# MonthCalendar_Controller_v0_9.net
KiCad netlist of a schematic drawn in EAGLE
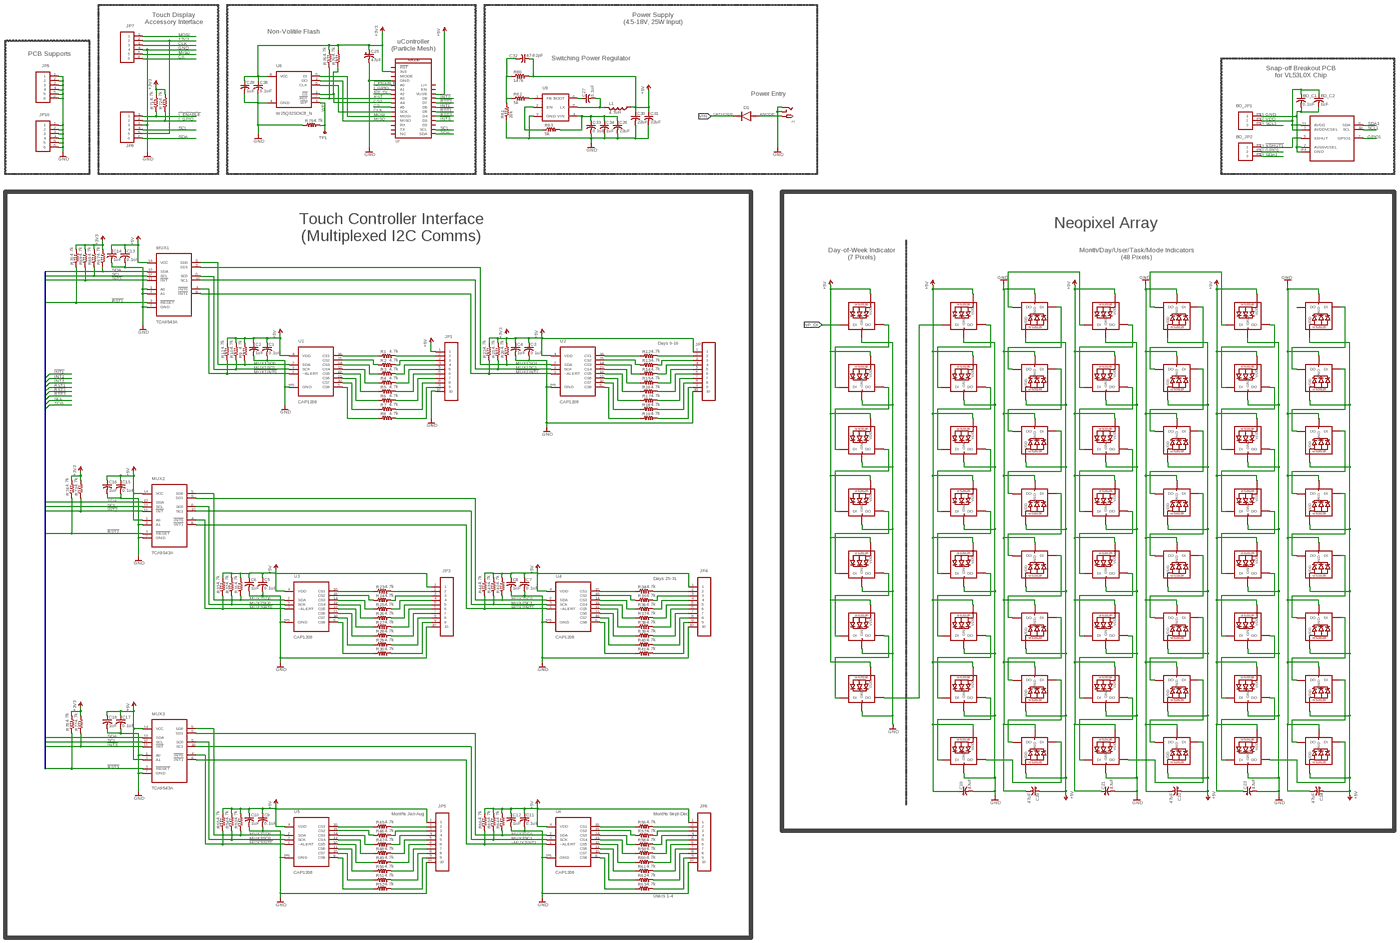
[diagram p0: schematic, sheet 1, overview]
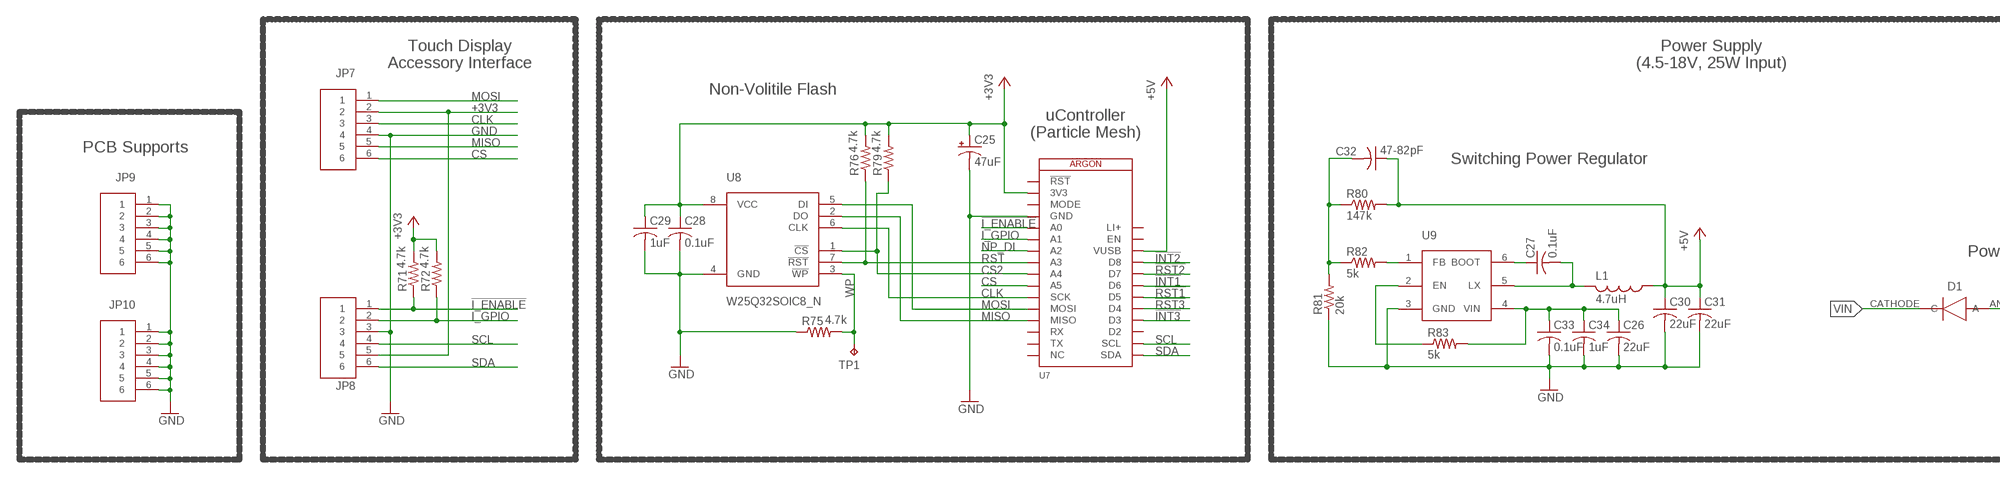
[diagram p1: schematic, sheet 1, part 1 of 4]
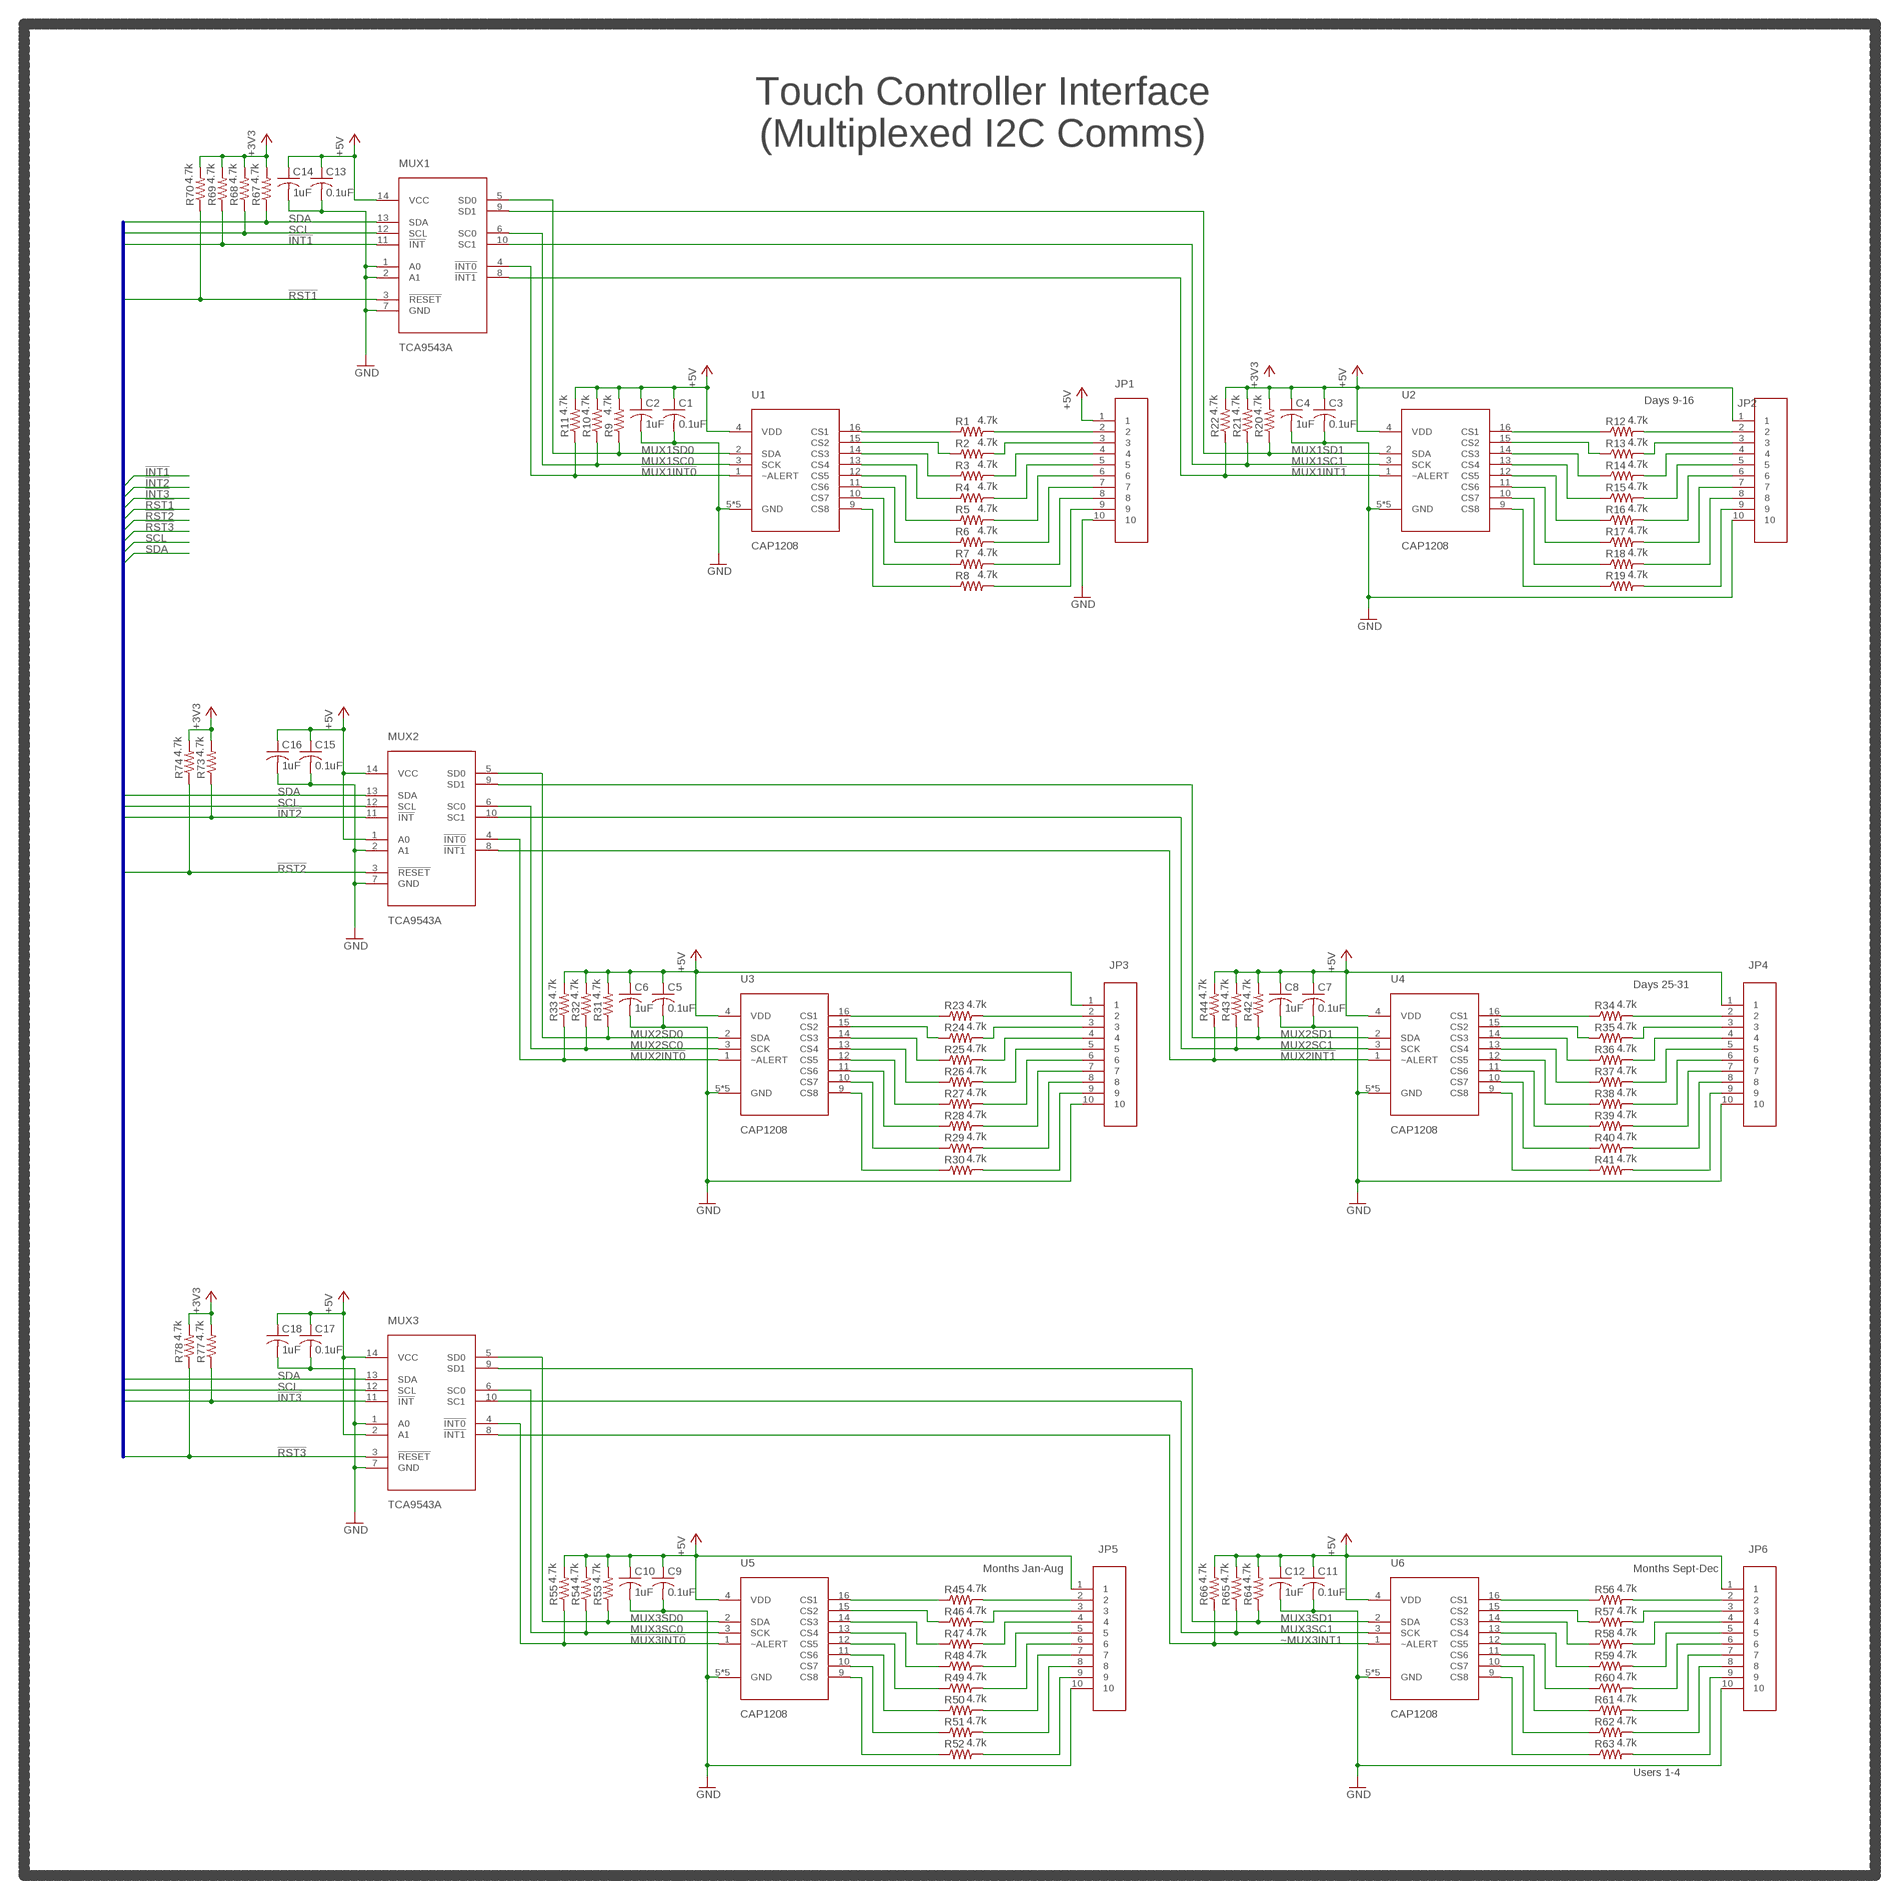
[diagram p2: schematic, sheet 1, part 2 of 4]
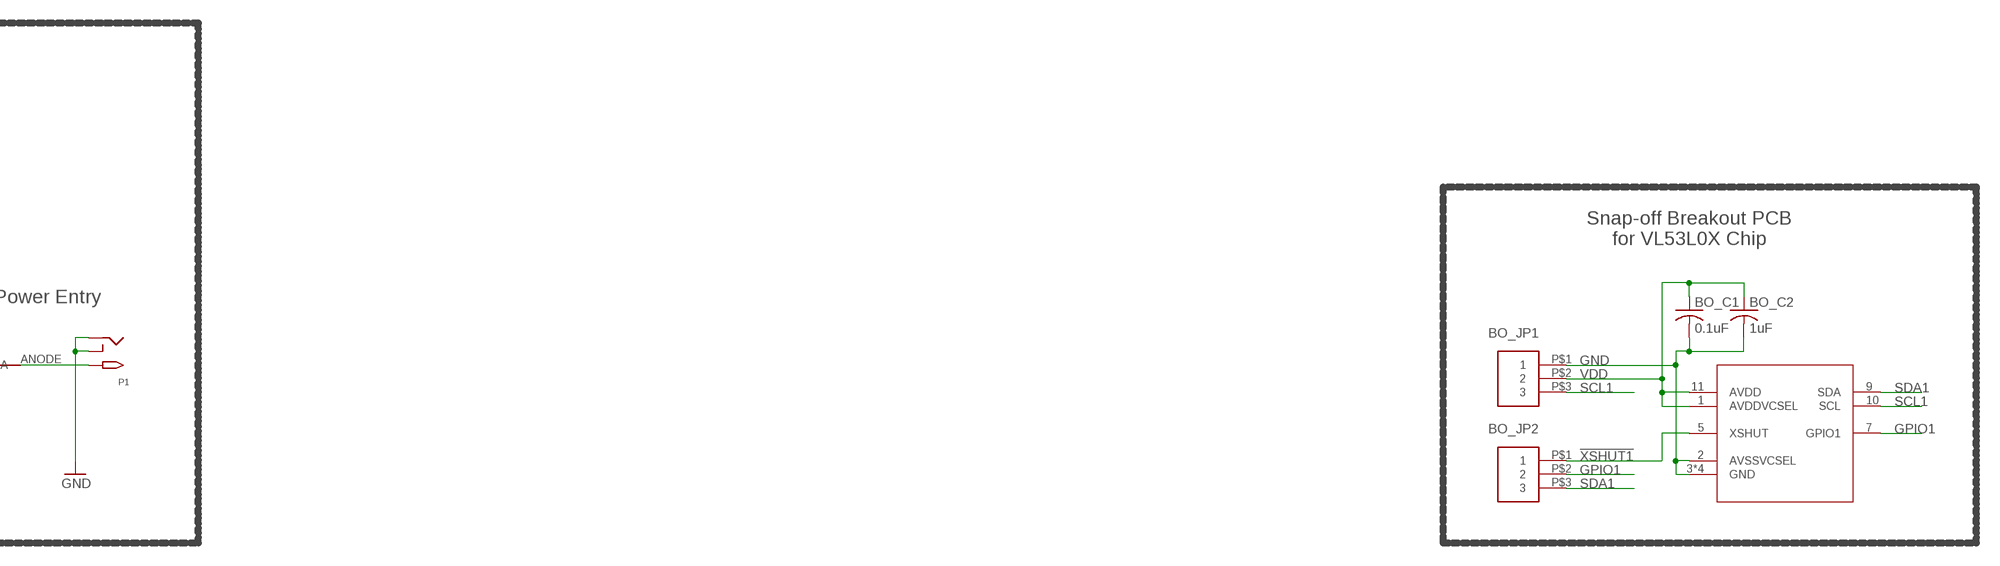
[diagram p3: schematic, sheet 1, part 3 of 4]
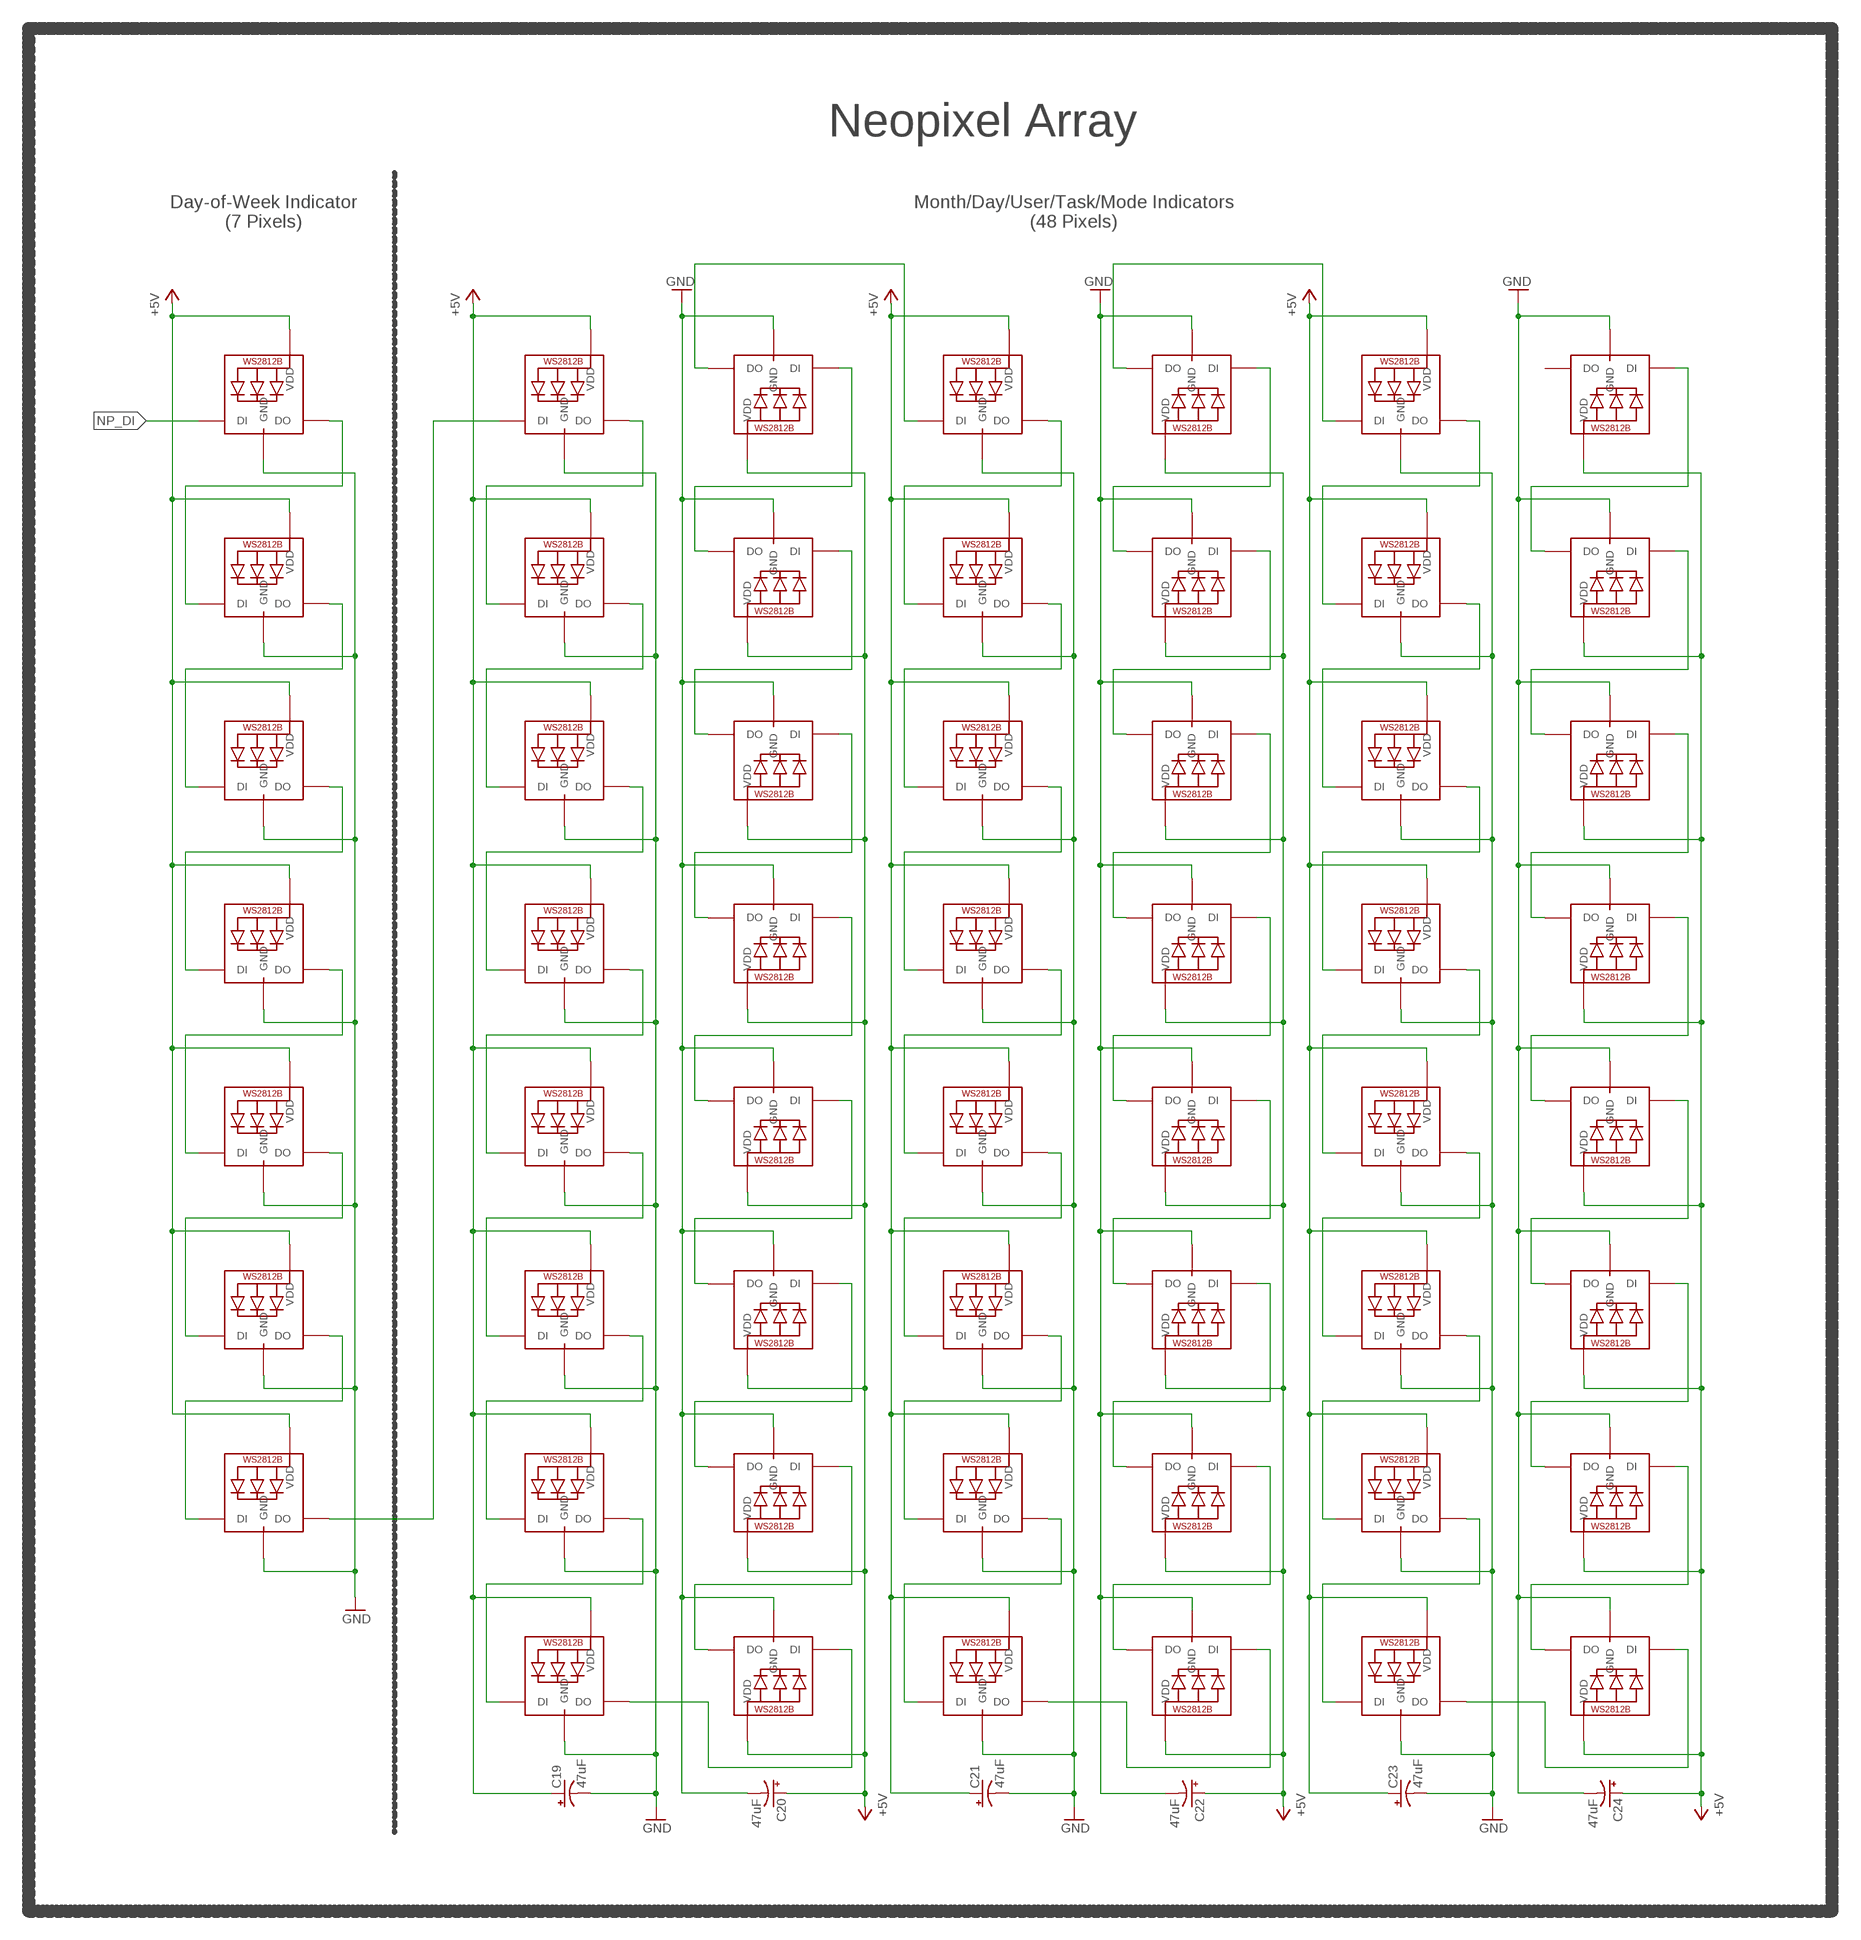
[diagram p4: schematic, sheet 1, part 4 of 4]

(export (version "E")
  (design (tool "Eeschema 10.0.6"))
  (components
    (comp (ref "BO_C1")
      (value "0.1uF")
      (footprint "eagle-import:C0603")
      (libsource (lib "eagle-import") (part "C-USC0603"))
    )
    (comp (ref "BO_C2")
      (value "1uF")
      (footprint "eagle-import:C0603")
      (libsource (lib "eagle-import") (part "C-USC0603"))
    )
    (comp (ref "BO_JP1")
      (value "PINHEAD_1X350MIL")
      (footprint "eagle-import:PINHEAD_1X3_50MIL")
      (libsource (lib "eagle-import") (part "PINHEAD_1X350MIL"))
    )
    (comp (ref "BO_JP2")
      (value "PINHEAD_1X350MIL")
      (footprint "eagle-import:PINHEAD_1X3_50MIL")
      (libsource (lib "eagle-import") (part "PINHEAD_1X350MIL"))
    )
    (comp (ref "BO_U1")
      (value "VL53L0X")
      (footprint "eagle-import:VL53L0X")
      (libsource (lib "eagle-import") (part "VL53L0X"))
    )
    (comp (ref "C1")
      (value "0.1uF")
      (footprint "eagle-import:C0603")
      (libsource (lib "eagle-import") (part "C-USC0603"))
    )
    (comp (ref "C2")
      (value "1uF")
      (footprint "eagle-import:C0603")
      (libsource (lib "eagle-import") (part "C-USC0603"))
    )
    (comp (ref "C3")
      (value "0.1uF")
      (footprint "eagle-import:C0603")
      (libsource (lib "eagle-import") (part "C-USC0603"))
    )
    (comp (ref "C4")
      (value "1uF")
      (footprint "eagle-import:C0603")
      (libsource (lib "eagle-import") (part "C-USC0603"))
    )
    (comp (ref "C5")
      (value "0.1uF")
      (footprint "eagle-import:C0603")
      (libsource (lib "eagle-import") (part "C-USC0603"))
    )
    (comp (ref "C6")
      (value "1uF")
      (footprint "eagle-import:C0603")
      (libsource (lib "eagle-import") (part "C-USC0603"))
    )
    (comp (ref "C7")
      (value "0.1uF")
      (footprint "eagle-import:C0603")
      (libsource (lib "eagle-import") (part "C-USC0603"))
    )
    (comp (ref "C8")
      (value "1uF")
      (footprint "eagle-import:C0603")
      (libsource (lib "eagle-import") (part "C-USC0603"))
    )
    (comp (ref "C9")
      (value "0.1uF")
      (footprint "eagle-import:C0603")
      (libsource (lib "eagle-import") (part "C-USC0603"))
    )
    (comp (ref "C10")
      (value "1uF")
      (footprint "eagle-import:C0603")
      (libsource (lib "eagle-import") (part "C-USC0603"))
    )
    (comp (ref "C11")
      (value "0.1uF")
      (footprint "eagle-import:C0603")
      (libsource (lib "eagle-import") (part "C-USC0603"))
    )
    (comp (ref "C12")
      (value "1uF")
      (footprint "eagle-import:C0603")
      (libsource (lib "eagle-import") (part "C-USC0603"))
    )
    (comp (ref "C13")
      (value "0.1uF")
      (footprint "eagle-import:C0603")
      (libsource (lib "eagle-import") (part "C-USC0603"))
    )
    (comp (ref "C14")
      (value "1uF")
      (footprint "eagle-import:C0603")
      (libsource (lib "eagle-import") (part "C-USC0603"))
    )
    (comp (ref "C15")
      (value "0.1uF")
      (footprint "eagle-import:C0603")
      (libsource (lib "eagle-import") (part "C-USC0603"))
    )
    (comp (ref "C16")
      (value "1uF")
      (footprint "eagle-import:C0603")
      (libsource (lib "eagle-import") (part "C-USC0603"))
    )
    (comp (ref "C17")
      (value "0.1uF")
      (footprint "eagle-import:C0603")
      (libsource (lib "eagle-import") (part "C-USC0603"))
    )
    (comp (ref "C18")
      (value "1uF")
      (footprint "eagle-import:C0603")
      (libsource (lib "eagle-import") (part "C-USC0603"))
    )
    (comp (ref "C19")
      (value "47uF")
      (footprint "eagle-import:EIA3216")
      (libsource (lib "eagle-import") (part "TANT-CAP1206"))
    )
    (comp (ref "C20")
      (value "47uF")
      (footprint "eagle-import:EIA3216")
      (libsource (lib "eagle-import") (part "TANT-CAP1206"))
    )
    (comp (ref "C21")
      (value "47uF")
      (footprint "eagle-import:EIA3216")
      (libsource (lib "eagle-import") (part "TANT-CAP1206"))
    )
    (comp (ref "C22")
      (value "47uF")
      (footprint "eagle-import:EIA3216")
      (libsource (lib "eagle-import") (part "TANT-CAP1206"))
    )
    (comp (ref "C23")
      (value "47uF")
      (footprint "eagle-import:EIA3216")
      (libsource (lib "eagle-import") (part "TANT-CAP1206"))
    )
    (comp (ref "C24")
      (value "47uF")
      (footprint "eagle-import:EIA3216")
      (libsource (lib "eagle-import") (part "TANT-CAP1206"))
    )
    (comp (ref "C25")
      (value "47uF")
      (footprint "eagle-import:EIA3216")
      (libsource (lib "eagle-import") (part "TANT-CAP1206"))
    )
    (comp (ref "C26")
      (value "22uF")
      (footprint "eagle-import:C1206")
      (libsource (lib "eagle-import") (part "resistor_mod_C-USC1206"))
    )
    (comp (ref "C27")
      (value "0.1uF")
      (footprint "eagle-import:C0603")
      (libsource (lib "eagle-import") (part "resistor_mod_C-USC0603"))
    )
    (comp (ref "C28")
      (value "0.1uF")
      (footprint "eagle-import:C0603")
      (libsource (lib "eagle-import") (part "C-USC0603"))
    )
    (comp (ref "C29")
      (value "1uF")
      (footprint "eagle-import:C0603")
      (libsource (lib "eagle-import") (part "C-USC0603"))
    )
    (comp (ref "C30")
      (value "22uF")
      (footprint "eagle-import:C1206")
      (libsource (lib "eagle-import") (part "resistor_mod_C-USC1206"))
    )
    (comp (ref "C31")
      (value "22uF")
      (footprint "eagle-import:C1206")
      (libsource (lib "eagle-import") (part "resistor_mod_C-USC1206"))
    )
    (comp (ref "C32")
      (value "47-82pF")
      (footprint "eagle-import:C0603")
      (libsource (lib "eagle-import") (part "resistor_mod_C-USC0603"))
    )
    (comp (ref "C33")
      (value "0.1uF")
      (footprint "eagle-import:C0603")
      (libsource (lib "eagle-import") (part "resistor_mod_C-USC0603"))
    )
    (comp (ref "C34")
      (value "1uF")
      (footprint "eagle-import:C0603")
      (libsource (lib "eagle-import") (part "resistor_mod_C-USC0603"))
    )
    (comp (ref "D1")
      (value "DIODE")
      (footprint "eagle-import:SOD-128")
      (libsource (lib "eagle-import") (part "DIODE"))
    )
    (comp (ref "JP1")
      (value "CON_10POS_1ROWHARWIN_M3531042")
      (footprint "eagle-import:CON_PINHEADER_10P_1R_TH_HARWIN_M50-3531042")
      (libsource (lib "eagle-import") (part "CON_10POS_1ROWHARWIN_M3531042"))
    )
    (comp (ref "JP2")
      (value "CON_10POS_1ROWHARWIN_M3531042")
      (footprint "eagle-import:CON_PINHEADER_10P_1R_TH_HARWIN_M50-3531042")
      (libsource (lib "eagle-import") (part "CON_10POS_1ROWHARWIN_M3531042"))
    )
    (comp (ref "JP3")
      (value "CON_10POS_1ROWHARWIN_M3531042")
      (footprint "eagle-import:CON_PINHEADER_10P_1R_TH_HARWIN_M50-3531042")
      (libsource (lib "eagle-import") (part "CON_10POS_1ROWHARWIN_M3531042"))
    )
    (comp (ref "JP4")
      (value "CON_10POS_1ROWHARWIN_M3531042")
      (footprint "eagle-import:CON_PINHEADER_10P_1R_TH_HARWIN_M50-3531042")
      (libsource (lib "eagle-import") (part "CON_10POS_1ROWHARWIN_M3531042"))
    )
    (comp (ref "JP5")
      (value "CON_10POS_1ROWHARWIN_M3531042")
      (footprint "eagle-import:CON_PINHEADER_10P_1R_TH_HARWIN_M50-3531042")
      (libsource (lib "eagle-import") (part "CON_10POS_1ROWHARWIN_M3531042"))
    )
    (comp (ref "JP6")
      (value "CON_10POS_1ROWHARWIN_M3531042")
      (footprint "eagle-import:CON_PINHEADER_10P_1R_TH_HARWIN_M50-3531042")
      (libsource (lib "eagle-import") (part "CON_10POS_1ROWHARWIN_M3531042"))
    )
    (comp (ref "JP7")
      (value "CON_6POS_1ROW6P1R_M50_35306")
      (footprint "eagle-import:CON_PINHEADER_6P_1R_TH_HARWIN_M50-3530642")
      (libsource (lib "eagle-import") (part "CON_6POS_1ROW6P1R_M50_35306"))
    )
    (comp (ref "JP8")
      (value "CON_6POS_1ROW6P1R_M50_35306")
      (footprint "eagle-import:CON_PINHEADER_6P_1R_TH_HARWIN_M50-3530642")
      (libsource (lib "eagle-import") (part "CON_6POS_1ROW6P1R_M50_35306"))
    )
    (comp (ref "JP9")
      (value "CON_6POS_1ROW6P1R_M50_35306")
      (footprint "eagle-import:CON_PINHEADER_6P_1R_TH_HARWIN_M50-3530642")
      (libsource (lib "eagle-import") (part "CON_6POS_1ROW6P1R_M50_35306"))
    )
    (comp (ref "JP10")
      (value "CON_6POS_1ROW6P1R_M50_35306")
      (footprint "eagle-import:CON_PINHEADER_6P_1R_TH_HARWIN_M50-3530642")
      (libsource (lib "eagle-import") (part "CON_6POS_1ROW6P1R_M50_35306"))
    )
    (comp (ref "L1")
      (value "4.7uH")
      (footprint "eagle-import:0207_5V")
      (libsource (lib "eagle-import") (part "L-US0207/5V"))
    )
    (comp (ref "LED1")
      (value "WS2812B5050")
      (footprint "eagle-import:WS2812B")
      (libsource (lib "eagle-import") (part "WS2812B5050"))
    )
    (comp (ref "LED2")
      (value "WS2812B5050")
      (footprint "eagle-import:WS2812B")
      (libsource (lib "eagle-import") (part "WS2812B5050"))
    )
    (comp (ref "LED3")
      (value "WS2812B5050")
      (footprint "eagle-import:WS2812B")
      (libsource (lib "eagle-import") (part "WS2812B5050"))
    )
    (comp (ref "LED4")
      (value "WS2812B5050")
      (footprint "eagle-import:WS2812B")
      (libsource (lib "eagle-import") (part "WS2812B5050"))
    )
    (comp (ref "LED5")
      (value "WS2812B5050")
      (footprint "eagle-import:WS2812B")
      (libsource (lib "eagle-import") (part "WS2812B5050"))
    )
    (comp (ref "LED6")
      (value "WS2812B5050")
      (footprint "eagle-import:WS2812B")
      (libsource (lib "eagle-import") (part "WS2812B5050"))
    )
    (comp (ref "LED7")
      (value "WS2812B5050")
      (footprint "eagle-import:WS2812B")
      (libsource (lib "eagle-import") (part "WS2812B5050"))
    )
    (comp (ref "LED8")
      (value "WS2812B5050")
      (footprint "eagle-import:WS2812B")
      (libsource (lib "eagle-import") (part "WS2812B5050"))
    )
    (comp (ref "LED9")
      (value "WS2812B5050")
      (footprint "eagle-import:WS2812B")
      (libsource (lib "eagle-import") (part "WS2812B5050"))
    )
    (comp (ref "LED10")
      (value "WS2812B5050")
      (footprint "eagle-import:WS2812B")
      (libsource (lib "eagle-import") (part "WS2812B5050"))
    )
    (comp (ref "LED11")
      (value "WS2812B5050")
      (footprint "eagle-import:WS2812B")
      (libsource (lib "eagle-import") (part "WS2812B5050"))
    )
    (comp (ref "LED12")
      (value "WS2812B5050")
      (footprint "eagle-import:WS2812B")
      (libsource (lib "eagle-import") (part "WS2812B5050"))
    )
    (comp (ref "LED13")
      (value "WS2812B5050")
      (footprint "eagle-import:WS2812B")
      (libsource (lib "eagle-import") (part "WS2812B5050"))
    )
    (comp (ref "LED14")
      (value "WS2812B5050")
      (footprint "eagle-import:WS2812B")
      (libsource (lib "eagle-import") (part "WS2812B5050"))
    )
    (comp (ref "LED15")
      (value "WS2812B5050")
      (footprint "eagle-import:WS2812B")
      (libsource (lib "eagle-import") (part "WS2812B5050"))
    )
    (comp (ref "LED16")
      (value "WS2812B5050")
      (footprint "eagle-import:WS2812B")
      (libsource (lib "eagle-import") (part "WS2812B5050"))
    )
    (comp (ref "LED17")
      (value "WS2812B5050")
      (footprint "eagle-import:WS2812B")
      (libsource (lib "eagle-import") (part "WS2812B5050"))
    )
    (comp (ref "LED18")
      (value "WS2812B5050")
      (footprint "eagle-import:WS2812B")
      (libsource (lib "eagle-import") (part "WS2812B5050"))
    )
    (comp (ref "LED19")
      (value "WS2812B5050")
      (footprint "eagle-import:WS2812B")
      (libsource (lib "eagle-import") (part "WS2812B5050"))
    )
    (comp (ref "LED20")
      (value "WS2812B5050")
      (footprint "eagle-import:WS2812B")
      (libsource (lib "eagle-import") (part "WS2812B5050"))
    )
    (comp (ref "LED21")
      (value "WS2812B5050")
      (footprint "eagle-import:WS2812B")
      (libsource (lib "eagle-import") (part "WS2812B5050"))
    )
    (comp (ref "LED22")
      (value "WS2812B5050")
      (footprint "eagle-import:WS2812B")
      (libsource (lib "eagle-import") (part "WS2812B5050"))
    )
    (comp (ref "LED23")
      (value "WS2812B5050")
      (footprint "eagle-import:WS2812B")
      (libsource (lib "eagle-import") (part "WS2812B5050"))
    )
    (comp (ref "LED24")
      (value "WS2812B5050")
      (footprint "eagle-import:WS2812B")
      (libsource (lib "eagle-import") (part "WS2812B5050"))
    )
    (comp (ref "LED25")
      (value "WS2812B5050")
      (footprint "eagle-import:WS2812B")
      (libsource (lib "eagle-import") (part "WS2812B5050"))
    )
    (comp (ref "LED26")
      (value "WS2812B5050")
      (footprint "eagle-import:WS2812B")
      (libsource (lib "eagle-import") (part "WS2812B5050"))
    )
    (comp (ref "LED27")
      (value "WS2812B5050")
      (footprint "eagle-import:WS2812B")
      (libsource (lib "eagle-import") (part "WS2812B5050"))
    )
    (comp (ref "LED28")
      (value "WS2812B5050")
      (footprint "eagle-import:WS2812B")
      (libsource (lib "eagle-import") (part "WS2812B5050"))
    )
    (comp (ref "LED29")
      (value "WS2812B5050")
      (footprint "eagle-import:WS2812B")
      (libsource (lib "eagle-import") (part "WS2812B5050"))
    )
    (comp (ref "LED30")
      (value "WS2812B5050")
      (footprint "eagle-import:WS2812B")
      (libsource (lib "eagle-import") (part "WS2812B5050"))
    )
    (comp (ref "LED31")
      (value "WS2812B5050")
      (footprint "eagle-import:WS2812B")
      (libsource (lib "eagle-import") (part "WS2812B5050"))
    )
    (comp (ref "LED32")
      (value "WS2812B5050")
      (footprint "eagle-import:WS2812B")
      (libsource (lib "eagle-import") (part "WS2812B5050"))
    )
    (comp (ref "LED33")
      (value "WS2812B5050")
      (footprint "eagle-import:WS2812B")
      (libsource (lib "eagle-import") (part "WS2812B5050"))
    )
    (comp (ref "LED34")
      (value "WS2812B5050")
      (footprint "eagle-import:WS2812B")
      (libsource (lib "eagle-import") (part "WS2812B5050"))
    )
    (comp (ref "LED35")
      (value "WS2812B5050")
      (footprint "eagle-import:WS2812B")
      (libsource (lib "eagle-import") (part "WS2812B5050"))
    )
    (comp (ref "LED36")
      (value "WS2812B5050")
      (footprint "eagle-import:WS2812B")
      (libsource (lib "eagle-import") (part "WS2812B5050"))
    )
    (comp (ref "LED37")
      (value "WS2812B5050")
      (footprint "eagle-import:WS2812B")
      (libsource (lib "eagle-import") (part "WS2812B5050"))
    )
    (comp (ref "LED38")
      (value "WS2812B5050")
      (footprint "eagle-import:WS2812B")
      (libsource (lib "eagle-import") (part "WS2812B5050"))
    )
    (comp (ref "LED39")
      (value "WS2812B5050")
      (footprint "eagle-import:WS2812B")
      (libsource (lib "eagle-import") (part "WS2812B5050"))
    )
    (comp (ref "LED40")
      (value "WS2812B5050")
      (footprint "eagle-import:WS2812B")
      (libsource (lib "eagle-import") (part "WS2812B5050"))
    )
    (comp (ref "LED41")
      (value "WS2812B5050")
      (footprint "eagle-import:WS2812B")
      (libsource (lib "eagle-import") (part "WS2812B5050"))
    )
    (comp (ref "LED42")
      (value "WS2812B5050")
      (footprint "eagle-import:WS2812B")
      (libsource (lib "eagle-import") (part "WS2812B5050"))
    )
    (comp (ref "LED43")
      (value "WS2812B5050")
      (footprint "eagle-import:WS2812B")
      (libsource (lib "eagle-import") (part "WS2812B5050"))
    )
    (comp (ref "LED44")
      (value "WS2812B5050")
      (footprint "eagle-import:WS2812B")
      (libsource (lib "eagle-import") (part "WS2812B5050"))
    )
    (comp (ref "LED45")
      (value "WS2812B5050")
      (footprint "eagle-import:WS2812B")
      (libsource (lib "eagle-import") (part "WS2812B5050"))
    )
    (comp (ref "LED46")
      (value "WS2812B5050")
      (footprint "eagle-import:WS2812B")
      (libsource (lib "eagle-import") (part "WS2812B5050"))
    )
    (comp (ref "LED47")
      (value "WS2812B5050")
      (footprint "eagle-import:WS2812B")
      (libsource (lib "eagle-import") (part "WS2812B5050"))
    )
    (comp (ref "LED48")
      (value "WS2812B5050")
      (footprint "eagle-import:WS2812B")
      (libsource (lib "eagle-import") (part "WS2812B5050"))
    )
    (comp (ref "LED49")
      (value "WS2812B5050")
      (footprint "eagle-import:WS2812B")
      (libsource (lib "eagle-import") (part "WS2812B5050"))
    )
    (comp (ref "LED50")
      (value "WS2812B5050")
      (footprint "eagle-import:WS2812B")
      (libsource (lib "eagle-import") (part "WS2812B5050"))
    )
    (comp (ref "LED51")
      (value "WS2812B5050")
      (footprint "eagle-import:WS2812B")
      (libsource (lib "eagle-import") (part "WS2812B5050"))
    )
    (comp (ref "LED52")
      (value "WS2812B5050")
      (footprint "eagle-import:WS2812B")
      (libsource (lib "eagle-import") (part "WS2812B5050"))
    )
    (comp (ref "LED53")
      (value "WS2812B5050")
      (footprint "eagle-import:WS2812B")
      (libsource (lib "eagle-import") (part "WS2812B5050"))
    )
    (comp (ref "LED54")
      (value "WS2812B5050")
      (footprint "eagle-import:WS2812B")
      (libsource (lib "eagle-import") (part "WS2812B5050"))
    )
    (comp (ref "LED55")
      (value "WS2812B5050")
      (footprint "eagle-import:WS2812B")
      (libsource (lib "eagle-import") (part "WS2812B5050"))
    )
    (comp (ref "MUX1")
      (value "TCA9543A")
      (footprint "eagle-import:TSSOP-14")
      (libsource (lib "eagle-import") (part "TCA9543A"))
    )
    (comp (ref "MUX2")
      (value "TCA9543A")
      (footprint "eagle-import:TSSOP-14")
      (libsource (lib "eagle-import") (part "TCA9543A"))
    )
    (comp (ref "MUX3")
      (value "TCA9543A")
      (footprint "eagle-import:TSSOP-14")
      (libsource (lib "eagle-import") (part "TCA9543A"))
    )
    (comp (ref "P1")
      (value "2.1MMJACKTHM")
      (footprint "eagle-import:PJ-102A")
      (libsource (lib "eagle-import") (part "2.1MMJACKTHM"))
    )
    (comp (ref "R1")
      (value "4.7k")
      (footprint "eagle-import:R0603")
      (libsource (lib "eagle-import") (part "R-US_R0603"))
    )
    (comp (ref "R2")
      (value "4.7k")
      (footprint "eagle-import:R0603")
      (libsource (lib "eagle-import") (part "R-US_R0603"))
    )
    (comp (ref "R3")
      (value "4.7k")
      (footprint "eagle-import:R0603")
      (libsource (lib "eagle-import") (part "R-US_R0603"))
    )
    (comp (ref "R4")
      (value "4.7k")
      (footprint "eagle-import:R0603")
      (libsource (lib "eagle-import") (part "R-US_R0603"))
    )
    (comp (ref "R5")
      (value "4.7k")
      (footprint "eagle-import:R0603")
      (libsource (lib "eagle-import") (part "R-US_R0603"))
    )
    (comp (ref "R6")
      (value "4.7k")
      (footprint "eagle-import:R0603")
      (libsource (lib "eagle-import") (part "R-US_R0603"))
    )
    (comp (ref "R7")
      (value "4.7k")
      (footprint "eagle-import:R0603")
      (libsource (lib "eagle-import") (part "R-US_R0603"))
    )
    (comp (ref "R8")
      (value "4.7k")
      (footprint "eagle-import:R0603")
      (libsource (lib "eagle-import") (part "R-US_R0603"))
    )
    (comp (ref "R9")
      (value "4.7k")
      (footprint "eagle-import:R0603")
      (libsource (lib "eagle-import") (part "R-US_R0603"))
    )
    (comp (ref "R10")
      (value "4.7k")
      (footprint "eagle-import:R0603")
      (libsource (lib "eagle-import") (part "R-US_R0603"))
    )
    (comp (ref "R11")
      (value "4.7k")
      (footprint "eagle-import:R0603")
      (libsource (lib "eagle-import") (part "R-US_R0603"))
    )
    (comp (ref "R12")
      (value "4.7k")
      (footprint "eagle-import:R0603")
      (libsource (lib "eagle-import") (part "R-US_R0603"))
    )
    (comp (ref "R13")
      (value "4.7k")
      (footprint "eagle-import:R0603")
      (libsource (lib "eagle-import") (part "R-US_R0603"))
    )
    (comp (ref "R14")
      (value "4.7k")
      (footprint "eagle-import:R0603")
      (libsource (lib "eagle-import") (part "R-US_R0603"))
    )
    (comp (ref "R15")
      (value "4.7k")
      (footprint "eagle-import:R0603")
      (libsource (lib "eagle-import") (part "R-US_R0603"))
    )
    (comp (ref "R16")
      (value "4.7k")
      (footprint "eagle-import:R0603")
      (libsource (lib "eagle-import") (part "R-US_R0603"))
    )
    (comp (ref "R17")
      (value "4.7k")
      (footprint "eagle-import:R0603")
      (libsource (lib "eagle-import") (part "R-US_R0603"))
    )
    (comp (ref "R18")
      (value "4.7k")
      (footprint "eagle-import:R0603")
      (libsource (lib "eagle-import") (part "R-US_R0603"))
    )
    (comp (ref "R19")
      (value "4.7k")
      (footprint "eagle-import:R0603")
      (libsource (lib "eagle-import") (part "R-US_R0603"))
    )
    (comp (ref "R20")
      (value "4.7k")
      (footprint "eagle-import:R0603")
      (libsource (lib "eagle-import") (part "R-US_R0603"))
    )
    (comp (ref "R21")
      (value "4.7k")
      (footprint "eagle-import:R0603")
      (libsource (lib "eagle-import") (part "R-US_R0603"))
    )
    (comp (ref "R22")
      (value "4.7k")
      (footprint "eagle-import:R0603")
      (libsource (lib "eagle-import") (part "R-US_R0603"))
    )
    (comp (ref "R23")
      (value "4.7k")
      (footprint "eagle-import:R0603")
      (libsource (lib "eagle-import") (part "R-US_R0603"))
    )
    (comp (ref "R24")
      (value "4.7k")
      (footprint "eagle-import:R0603")
      (libsource (lib "eagle-import") (part "R-US_R0603"))
    )
    (comp (ref "R25")
      (value "4.7k")
      (footprint "eagle-import:R0603")
      (libsource (lib "eagle-import") (part "R-US_R0603"))
    )
    (comp (ref "R26")
      (value "4.7k")
      (footprint "eagle-import:R0603")
      (libsource (lib "eagle-import") (part "R-US_R0603"))
    )
    (comp (ref "R27")
      (value "4.7k")
      (footprint "eagle-import:R0603")
      (libsource (lib "eagle-import") (part "R-US_R0603"))
    )
    (comp (ref "R28")
      (value "4.7k")
      (footprint "eagle-import:R0603")
      (libsource (lib "eagle-import") (part "R-US_R0603"))
    )
    (comp (ref "R29")
      (value "4.7k")
      (footprint "eagle-import:R0603")
      (libsource (lib "eagle-import") (part "R-US_R0603"))
    )
    (comp (ref "R30")
      (value "4.7k")
      (footprint "eagle-import:R0603")
      (libsource (lib "eagle-import") (part "R-US_R0603"))
    )
    (comp (ref "R31")
      (value "4.7k")
      (footprint "eagle-import:R0603")
      (libsource (lib "eagle-import") (part "R-US_R0603"))
    )
    (comp (ref "R32")
      (value "4.7k")
      (footprint "eagle-import:R0603")
      (libsource (lib "eagle-import") (part "R-US_R0603"))
    )
    (comp (ref "R33")
      (value "4.7k")
      (footprint "eagle-import:R0603")
      (libsource (lib "eagle-import") (part "R-US_R0603"))
    )
    (comp (ref "R34")
      (value "4.7k")
      (footprint "eagle-import:R0603")
      (libsource (lib "eagle-import") (part "R-US_R0603"))
    )
    (comp (ref "R35")
      (value "4.7k")
      (footprint "eagle-import:R0603")
      (libsource (lib "eagle-import") (part "R-US_R0603"))
    )
    (comp (ref "R36")
      (value "4.7k")
      (footprint "eagle-import:R0603")
      (libsource (lib "eagle-import") (part "R-US_R0603"))
    )
    (comp (ref "R37")
      (value "4.7k")
      (footprint "eagle-import:R0603")
      (libsource (lib "eagle-import") (part "R-US_R0603"))
    )
    (comp (ref "R38")
      (value "4.7k")
      (footprint "eagle-import:R0603")
      (libsource (lib "eagle-import") (part "R-US_R0603"))
    )
    (comp (ref "R39")
      (value "4.7k")
      (footprint "eagle-import:R0603")
      (libsource (lib "eagle-import") (part "R-US_R0603"))
    )
    (comp (ref "R40")
      (value "4.7k")
      (footprint "eagle-import:R0603")
      (libsource (lib "eagle-import") (part "R-US_R0603"))
    )
    (comp (ref "R41")
      (value "4.7k")
      (footprint "eagle-import:R0603")
      (libsource (lib "eagle-import") (part "R-US_R0603"))
    )
    (comp (ref "R42")
      (value "4.7k")
      (footprint "eagle-import:R0603")
      (libsource (lib "eagle-import") (part "R-US_R0603"))
    )
    (comp (ref "R43")
      (value "4.7k")
      (footprint "eagle-import:R0603")
      (libsource (lib "eagle-import") (part "R-US_R0603"))
    )
    (comp (ref "R44")
      (value "4.7k")
      (footprint "eagle-import:R0603")
      (libsource (lib "eagle-import") (part "R-US_R0603"))
    )
    (comp (ref "R45")
      (value "4.7k")
      (footprint "eagle-import:R0603")
      (libsource (lib "eagle-import") (part "R-US_R0603"))
    )
    (comp (ref "R46")
      (value "4.7k")
      (footprint "eagle-import:R0603")
      (libsource (lib "eagle-import") (part "R-US_R0603"))
    )
    (comp (ref "R47")
      (value "4.7k")
      (footprint "eagle-import:R0603")
      (libsource (lib "eagle-import") (part "R-US_R0603"))
    )
    (comp (ref "R48")
      (value "4.7k")
      (footprint "eagle-import:R0603")
      (libsource (lib "eagle-import") (part "R-US_R0603"))
    )
    (comp (ref "R49")
      (value "4.7k")
      (footprint "eagle-import:R0603")
      (libsource (lib "eagle-import") (part "R-US_R0603"))
    )
    (comp (ref "R50")
      (value "4.7k")
      (footprint "eagle-import:R0603")
      (libsource (lib "eagle-import") (part "R-US_R0603"))
    )
    (comp (ref "R51")
      (value "4.7k")
      (footprint "eagle-import:R0603")
      (libsource (lib "eagle-import") (part "R-US_R0603"))
    )
    (comp (ref "R52")
      (value "4.7k")
      (footprint "eagle-import:R0603")
      (libsource (lib "eagle-import") (part "R-US_R0603"))
    )
    (comp (ref "R53")
      (value "4.7k")
      (footprint "eagle-import:R0603")
      (libsource (lib "eagle-import") (part "R-US_R0603"))
    )
    (comp (ref "R54")
      (value "4.7k")
      (footprint "eagle-import:R0603")
      (libsource (lib "eagle-import") (part "R-US_R0603"))
    )
    (comp (ref "R55")
      (value "4.7k")
      (footprint "eagle-import:R0603")
      (libsource (lib "eagle-import") (part "R-US_R0603"))
    )
    (comp (ref "R56")
      (value "4.7k")
      (footprint "eagle-import:R0603")
      (libsource (lib "eagle-import") (part "R-US_R0603"))
    )
    (comp (ref "R57")
      (value "4.7k")
      (footprint "eagle-import:R0603")
      (libsource (lib "eagle-import") (part "R-US_R0603"))
    )
    (comp (ref "R58")
      (value "4.7k")
      (footprint "eagle-import:R0603")
      (libsource (lib "eagle-import") (part "R-US_R0603"))
    )
    (comp (ref "R59")
      (value "4.7k")
      (footprint "eagle-import:R0603")
      (libsource (lib "eagle-import") (part "R-US_R0603"))
    )
    (comp (ref "R60")
      (value "4.7k")
      (footprint "eagle-import:R0603")
      (libsource (lib "eagle-import") (part "R-US_R0603"))
    )
    (comp (ref "R61")
      (value "4.7k")
      (footprint "eagle-import:R0603")
      (libsource (lib "eagle-import") (part "R-US_R0603"))
    )
    (comp (ref "R62")
      (value "4.7k")
      (footprint "eagle-import:R0603")
      (libsource (lib "eagle-import") (part "R-US_R0603"))
    )
    (comp (ref "R63")
      (value "4.7k")
      (footprint "eagle-import:R0603")
      (libsource (lib "eagle-import") (part "R-US_R0603"))
    )
    (comp (ref "R64")
      (value "4.7k")
      (footprint "eagle-import:R0603")
      (libsource (lib "eagle-import") (part "R-US_R0603"))
    )
    (comp (ref "R65")
      (value "4.7k")
      (footprint "eagle-import:R0603")
      (libsource (lib "eagle-import") (part "R-US_R0603"))
    )
    (comp (ref "R66")
      (value "4.7k")
      (footprint "eagle-import:R0603")
      (libsource (lib "eagle-import") (part "R-US_R0603"))
    )
    (comp (ref "R67")
      (value "4.7k")
      (footprint "eagle-import:R0603")
      (libsource (lib "eagle-import") (part "R-US_R0603"))
    )
    (comp (ref "R68")
      (value "4.7k")
      (footprint "eagle-import:R0603")
      (libsource (lib "eagle-import") (part "R-US_R0603"))
    )
    (comp (ref "R69")
      (value "4.7k")
      (footprint "eagle-import:R0603")
      (libsource (lib "eagle-import") (part "R-US_R0603"))
    )
    (comp (ref "R70")
      (value "4.7k")
      (footprint "eagle-import:R0603")
      (libsource (lib "eagle-import") (part "R-US_R0603"))
    )
    (comp (ref "R71")
      (value "4.7k")
      (footprint "eagle-import:R0603")
      (libsource (lib "eagle-import") (part "R-US_R0603"))
    )
    (comp (ref "R72")
      (value "4.7k")
      (footprint "eagle-import:R0603")
      (libsource (lib "eagle-import") (part "R-US_R0603"))
    )
    (comp (ref "R73")
      (value "4.7k")
      (footprint "eagle-import:R0603")
      (libsource (lib "eagle-import") (part "R-US_R0603"))
    )
    (comp (ref "R74")
      (value "4.7k")
      (footprint "eagle-import:R0603")
      (libsource (lib "eagle-import") (part "R-US_R0603"))
    )
    (comp (ref "R75")
      (value "4.7k")
      (footprint "eagle-import:R0603")
      (libsource (lib "eagle-import") (part "R-US_R0603"))
    )
    (comp (ref "R76")
      (value "4.7k")
      (footprint "eagle-import:R0603")
      (libsource (lib "eagle-import") (part "R-US_R0603"))
    )
    (comp (ref "R77")
      (value "4.7k")
      (footprint "eagle-import:R0603")
      (libsource (lib "eagle-import") (part "R-US_R0603"))
    )
    (comp (ref "R78")
      (value "4.7k")
      (footprint "eagle-import:R0603")
      (libsource (lib "eagle-import") (part "R-US_R0603"))
    )
    (comp (ref "R79")
      (value "4.7k")
      (footprint "eagle-import:R0603")
      (libsource (lib "eagle-import") (part "R-US_R0603"))
    )
    (comp (ref "R80")
      (value "147k")
      (footprint "eagle-import:R0603")
      (libsource (lib "eagle-import") (part "resistor_mod_R-US_R0603"))
    )
    (comp (ref "R81")
      (value "20k")
      (footprint "eagle-import:R0603")
      (libsource (lib "eagle-import") (part "resistor_mod_R-US_R0603"))
    )
    (comp (ref "R82")
      (value "5k")
      (footprint "eagle-import:R0603")
      (libsource (lib "eagle-import") (part "resistor_mod_R-US_R0603"))
    )
    (comp (ref "R83")
      (value "5k")
      (footprint "eagle-import:R0603")
      (libsource (lib "eagle-import") (part "resistor_mod_R-US_R0603"))
    )
    (comp (ref "TP1")
      (value "TPTP20SQ")
      (footprint "eagle-import:TP20SQ")
      (libsource (lib "eagle-import") (part "TPTP20SQ"))
    )
    (comp (ref "U1")
      (value "CAP1208")
      (footprint "eagle-import:QFN-16-3X3")
      (libsource (lib "eagle-import") (part "CAP1208"))
    )
    (comp (ref "U2")
      (value "CAP1208")
      (footprint "eagle-import:QFN-16-3X3")
      (libsource (lib "eagle-import") (part "CAP1208"))
    )
    (comp (ref "U3")
      (value "CAP1208")
      (footprint "eagle-import:QFN-16-3X3")
      (libsource (lib "eagle-import") (part "CAP1208"))
    )
    (comp (ref "U4")
      (value "CAP1208")
      (footprint "eagle-import:QFN-16-3X3")
      (libsource (lib "eagle-import") (part "CAP1208"))
    )
    (comp (ref "U5")
      (value "CAP1208")
      (footprint "eagle-import:QFN-16-3X3")
      (libsource (lib "eagle-import") (part "CAP1208"))
    )
    (comp (ref "U6")
      (value "CAP1208")
      (footprint "eagle-import:QFN-16-3X3")
      (libsource (lib "eagle-import") (part "CAP1208"))
    )
    (comp (ref "U7")
      (value "ARGON")
      (footprint "eagle-import:ARGON")
      (libsource (lib "eagle-import") (part "ARGON"))
    )
    (comp (ref "U8")
      (value "W25Q32SOIC8_N")
      (footprint "eagle-import:SOIC-8_NARROW")
      (libsource (lib "eagle-import") (part "W25Q32SOIC8_N"))
    )
    (comp (ref "U9")
      (value "RT6255AHGJ6FCT-ND")
      (footprint "eagle-import:SOT-23-6")
      (libsource (lib "eagle-import") (part "RT6255A/B_J6F"))
    )
  )
  (nets
    (net (code "1") (name "+3V3") (class "Default")
      (node (ref "C25") (pin "A") (pinfunction "+_A") (pintype "passive"))
      (node (ref "C28") (pin "1") (pinfunction "1_1") (pintype "passive"))
      (node (ref "C29") (pin "1") (pinfunction "1_1") (pintype "passive"))
      (node (ref "JP7") (pin "2") (pinfunction "2_2") (pintype "bidirectional"))
      (node (ref "JP8") (pin "5") (pinfunction "5_5") (pintype "bidirectional"))
      (node (ref "R67") (pin "2") (pinfunction "2_2") (pintype "passive"))
      (node (ref "R68") (pin "2") (pinfunction "2_2") (pintype "passive"))
      (node (ref "R69") (pin "2") (pinfunction "2_2") (pintype "passive"))
      (node (ref "R70") (pin "2") (pinfunction "2_2") (pintype "passive"))
      (node (ref "R71") (pin "2") (pinfunction "2_2") (pintype "passive"))
      (node (ref "R72") (pin "2") (pinfunction "2_2") (pintype "passive"))
      (node (ref "R73") (pin "2") (pinfunction "2_2") (pintype "passive"))
      (node (ref "R74") (pin "2") (pinfunction "2_2") (pintype "passive"))
      (node (ref "R76") (pin "2") (pinfunction "2_2") (pintype "passive"))
      (node (ref "R77") (pin "2") (pinfunction "2_2") (pintype "passive"))
      (node (ref "R78") (pin "2") (pinfunction "2_2") (pintype "passive"))
      (node (ref "R79") (pin "2") (pinfunction "2_2") (pintype "passive"))
      (node (ref "U7") (pin "2") (pinfunction "3V3_2") (pintype "power_in"))
      (node (ref "U8") (pin "8") (pinfunction "VCC_8") (pintype "power_in"))
    )
    (net (code "2") (name "+5V") (class "Default")
      (node (ref "C1") (pin "1") (pinfunction "1_1") (pintype "passive"))
      (node (ref "C10") (pin "1") (pinfunction "1_1") (pintype "passive"))
      (node (ref "C11") (pin "1") (pinfunction "1_1") (pintype "passive"))
      (node (ref "C12") (pin "1") (pinfunction "1_1") (pintype "passive"))
      (node (ref "C13") (pin "1") (pinfunction "1_1") (pintype "passive"))
      (node (ref "C14") (pin "1") (pinfunction "1_1") (pintype "passive"))
      (node (ref "C15") (pin "1") (pinfunction "1_1") (pintype "passive"))
      (node (ref "C16") (pin "1") (pinfunction "1_1") (pintype "passive"))
      (node (ref "C17") (pin "1") (pinfunction "1_1") (pintype "passive"))
      (node (ref "C18") (pin "1") (pinfunction "1_1") (pintype "passive"))
      (node (ref "C19") (pin "A") (pinfunction "+_A") (pintype "passive"))
      (node (ref "C2") (pin "1") (pinfunction "1_1") (pintype "passive"))
      (node (ref "C20") (pin "A") (pinfunction "+_A") (pintype "passive"))
      (node (ref "C21") (pin "A") (pinfunction "+_A") (pintype "passive"))
      (node (ref "C22") (pin "A") (pinfunction "+_A") (pintype "passive"))
      (node (ref "C23") (pin "A") (pinfunction "+_A") (pintype "passive"))
      (node (ref "C24") (pin "A") (pinfunction "+_A") (pintype "passive"))
      (node (ref "C3") (pin "1") (pinfunction "1_1") (pintype "passive"))
      (node (ref "C30") (pin "1") (pinfunction "1_1") (pintype "passive"))
      (node (ref "C31") (pin "1") (pinfunction "1_1") (pintype "passive"))
      (node (ref "C32") (pin "1") (pinfunction "1_1") (pintype "passive"))
      (node (ref "C4") (pin "1") (pinfunction "1_1") (pintype "passive"))
      (node (ref "C5") (pin "1") (pinfunction "1_1") (pintype "passive"))
      (node (ref "C6") (pin "1") (pinfunction "1_1") (pintype "passive"))
      (node (ref "C7") (pin "1") (pinfunction "1_1") (pintype "passive"))
      (node (ref "C8") (pin "1") (pinfunction "1_1") (pintype "passive"))
      (node (ref "C9") (pin "1") (pinfunction "1_1") (pintype "passive"))
      (node (ref "JP1") (pin "1") (pinfunction "1_1") (pintype "bidirectional"))
      (node (ref "JP2") (pin "1") (pinfunction "1_1") (pintype "bidirectional"))
      (node (ref "JP3") (pin "1") (pinfunction "1_1") (pintype "bidirectional"))
      (node (ref "JP4") (pin "1") (pinfunction "1_1") (pintype "bidirectional"))
      (node (ref "JP5") (pin "1") (pinfunction "1_1") (pintype "bidirectional"))
      (node (ref "JP6") (pin "1") (pinfunction "1_1") (pintype "bidirectional"))
      (node (ref "L1") (pin "1") (pinfunction "1_1") (pintype "passive"))
      (node (ref "LED1") (pin "1-VDD") (pinfunction "VDD_1-VDD") (pintype "power_in"))
      (node (ref "LED10") (pin "1-VDD") (pinfunction "VDD_1-VDD") (pintype "power_in"))
      (node (ref "LED11") (pin "1-VDD") (pinfunction "VDD_1-VDD") (pintype "power_in"))
      (node (ref "LED12") (pin "1-VDD") (pinfunction "VDD_1-VDD") (pintype "power_in"))
      (node (ref "LED13") (pin "1-VDD") (pinfunction "VDD_1-VDD") (pintype "power_in"))
      (node (ref "LED14") (pin "1-VDD") (pinfunction "VDD_1-VDD") (pintype "power_in"))
      (node (ref "LED15") (pin "1-VDD") (pinfunction "VDD_1-VDD") (pintype "power_in"))
      (node (ref "LED16") (pin "1-VDD") (pinfunction "VDD_1-VDD") (pintype "power_in"))
      (node (ref "LED17") (pin "1-VDD") (pinfunction "VDD_1-VDD") (pintype "power_in"))
      (node (ref "LED18") (pin "1-VDD") (pinfunction "VDD_1-VDD") (pintype "power_in"))
      (node (ref "LED19") (pin "1-VDD") (pinfunction "VDD_1-VDD") (pintype "power_in"))
      (node (ref "LED2") (pin "1-VDD") (pinfunction "VDD_1-VDD") (pintype "power_in"))
      (node (ref "LED20") (pin "1-VDD") (pinfunction "VDD_1-VDD") (pintype "power_in"))
      (node (ref "LED21") (pin "1-VDD") (pinfunction "VDD_1-VDD") (pintype "power_in"))
      (node (ref "LED22") (pin "1-VDD") (pinfunction "VDD_1-VDD") (pintype "power_in"))
      (node (ref "LED23") (pin "1-VDD") (pinfunction "VDD_1-VDD") (pintype "power_in"))
      (node (ref "LED24") (pin "1-VDD") (pinfunction "VDD_1-VDD") (pintype "power_in"))
      (node (ref "LED25") (pin "1-VDD") (pinfunction "VDD_1-VDD") (pintype "power_in"))
      (node (ref "LED26") (pin "1-VDD") (pinfunction "VDD_1-VDD") (pintype "power_in"))
      (node (ref "LED27") (pin "1-VDD") (pinfunction "VDD_1-VDD") (pintype "power_in"))
      (node (ref "LED28") (pin "1-VDD") (pinfunction "VDD_1-VDD") (pintype "power_in"))
      (node (ref "LED29") (pin "1-VDD") (pinfunction "VDD_1-VDD") (pintype "power_in"))
      (node (ref "LED3") (pin "1-VDD") (pinfunction "VDD_1-VDD") (pintype "power_in"))
      (node (ref "LED30") (pin "1-VDD") (pinfunction "VDD_1-VDD") (pintype "power_in"))
      (node (ref "LED31") (pin "1-VDD") (pinfunction "VDD_1-VDD") (pintype "power_in"))
      (node (ref "LED32") (pin "1-VDD") (pinfunction "VDD_1-VDD") (pintype "power_in"))
      (node (ref "LED33") (pin "1-VDD") (pinfunction "VDD_1-VDD") (pintype "power_in"))
      (node (ref "LED34") (pin "1-VDD") (pinfunction "VDD_1-VDD") (pintype "power_in"))
      (node (ref "LED35") (pin "1-VDD") (pinfunction "VDD_1-VDD") (pintype "power_in"))
      (node (ref "LED36") (pin "1-VDD") (pinfunction "VDD_1-VDD") (pintype "power_in"))
      (node (ref "LED37") (pin "1-VDD") (pinfunction "VDD_1-VDD") (pintype "power_in"))
      (node (ref "LED38") (pin "1-VDD") (pinfunction "VDD_1-VDD") (pintype "power_in"))
      (node (ref "LED39") (pin "1-VDD") (pinfunction "VDD_1-VDD") (pintype "power_in"))
      (node (ref "LED4") (pin "1-VDD") (pinfunction "VDD_1-VDD") (pintype "power_in"))
      (node (ref "LED40") (pin "1-VDD") (pinfunction "VDD_1-VDD") (pintype "power_in"))
      (node (ref "LED41") (pin "1-VDD") (pinfunction "VDD_1-VDD") (pintype "power_in"))
      (node (ref "LED42") (pin "1-VDD") (pinfunction "VDD_1-VDD") (pintype "power_in"))
      (node (ref "LED43") (pin "1-VDD") (pinfunction "VDD_1-VDD") (pintype "power_in"))
      (node (ref "LED44") (pin "1-VDD") (pinfunction "VDD_1-VDD") (pintype "power_in"))
      (node (ref "LED45") (pin "1-VDD") (pinfunction "VDD_1-VDD") (pintype "power_in"))
      (node (ref "LED46") (pin "1-VDD") (pinfunction "VDD_1-VDD") (pintype "power_in"))
      (node (ref "LED47") (pin "1-VDD") (pinfunction "VDD_1-VDD") (pintype "power_in"))
      (node (ref "LED48") (pin "1-VDD") (pinfunction "VDD_1-VDD") (pintype "power_in"))
      (node (ref "LED49") (pin "1-VDD") (pinfunction "VDD_1-VDD") (pintype "power_in"))
      (node (ref "LED5") (pin "1-VDD") (pinfunction "VDD_1-VDD") (pintype "power_in"))
      (node (ref "LED50") (pin "1-VDD") (pinfunction "VDD_1-VDD") (pintype "power_in"))
      (node (ref "LED51") (pin "1-VDD") (pinfunction "VDD_1-VDD") (pintype "power_in"))
      (node (ref "LED52") (pin "1-VDD") (pinfunction "VDD_1-VDD") (pintype "power_in"))
      (node (ref "LED53") (pin "1-VDD") (pinfunction "VDD_1-VDD") (pintype "power_in"))
      (node (ref "LED54") (pin "1-VDD") (pinfunction "VDD_1-VDD") (pintype "power_in"))
      (node (ref "LED55") (pin "1-VDD") (pinfunction "VDD_1-VDD") (pintype "power_in"))
      (node (ref "LED6") (pin "1-VDD") (pinfunction "VDD_1-VDD") (pintype "power_in"))
      (node (ref "LED7") (pin "1-VDD") (pinfunction "VDD_1-VDD") (pintype "power_in"))
      (node (ref "LED8") (pin "1-VDD") (pinfunction "VDD_1-VDD") (pintype "power_in"))
      (node (ref "LED9") (pin "1-VDD") (pinfunction "VDD_1-VDD") (pintype "power_in"))
      (node (ref "MUX1") (pin "14") (pinfunction "VCC_14") (pintype "power_in"))
      (node (ref "MUX2") (pin "1") (pinfunction "A0_1") (pintype "input"))
      (node (ref "MUX2") (pin "14") (pinfunction "VCC_14") (pintype "power_in"))
      (node (ref "MUX3") (pin "14") (pinfunction "VCC_14") (pintype "power_in"))
      (node (ref "MUX3") (pin "2") (pinfunction "A1_2") (pintype "input"))
      (node (ref "R10") (pin "2") (pinfunction "2_2") (pintype "passive"))
      (node (ref "R11") (pin "2") (pinfunction "2_2") (pintype "passive"))
      (node (ref "R20") (pin "2") (pinfunction "2_2") (pintype "passive"))
      (node (ref "R21") (pin "2") (pinfunction "2_2") (pintype "passive"))
      (node (ref "R22") (pin "2") (pinfunction "2_2") (pintype "passive"))
      (node (ref "R31") (pin "2") (pinfunction "2_2") (pintype "passive"))
      (node (ref "R32") (pin "2") (pinfunction "2_2") (pintype "passive"))
      (node (ref "R33") (pin "2") (pinfunction "2_2") (pintype "passive"))
      (node (ref "R42") (pin "2") (pinfunction "2_2") (pintype "passive"))
      (node (ref "R43") (pin "2") (pinfunction "2_2") (pintype "passive"))
      (node (ref "R44") (pin "2") (pinfunction "2_2") (pintype "passive"))
      (node (ref "R53") (pin "2") (pinfunction "2_2") (pintype "passive"))
      (node (ref "R54") (pin "2") (pinfunction "2_2") (pintype "passive"))
      (node (ref "R55") (pin "2") (pinfunction "2_2") (pintype "passive"))
      (node (ref "R64") (pin "2") (pinfunction "2_2") (pintype "passive"))
      (node (ref "R65") (pin "2") (pinfunction "2_2") (pintype "passive"))
      (node (ref "R66") (pin "2") (pinfunction "2_2") (pintype "passive"))
      (node (ref "R80") (pin "2") (pinfunction "2_2") (pintype "passive"))
      (node (ref "R9") (pin "2") (pinfunction "2_2") (pintype "passive"))
      (node (ref "U1") (pin "4") (pinfunction "VDD_4") (pintype "power_in"))
      (node (ref "U2") (pin "4") (pinfunction "VDD_4") (pintype "power_in"))
      (node (ref "U3") (pin "4") (pinfunction "VDD_4") (pintype "power_in"))
      (node (ref "U4") (pin "4") (pinfunction "VDD_4") (pintype "power_in"))
      (node (ref "U5") (pin "4") (pinfunction "VDD_4") (pintype "power_in"))
      (node (ref "U6") (pin "4") (pinfunction "VDD_4") (pintype "power_in"))
      (node (ref "U7") (pin "26") (pinfunction "VUSB_26") (pintype "power_in"))
    )
    (net (code "3") (name "/CLK") (class "Default")
      (node (ref "JP7") (pin "3") (pinfunction "3_3") (pintype "bidirectional"))
      (node (ref "U7") (pin "11") (pinfunction "SCK_11") (pintype "bidirectional"))
      (node (ref "U8") (pin "6") (pinfunction "CLK_6") (pintype "input"))
    )
    (net (code "4") (name "/CS") (class "Default")
      (node (ref "JP7") (pin "6") (pinfunction "6_6") (pintype "bidirectional"))
      (node (ref "U7") (pin "10") (pinfunction "A5_10") (pintype "bidirectional"))
    )
    (net (code "5") (name "/CS2") (class "Default")
      (node (ref "R79") (pin "1") (pinfunction "1_1") (pintype "passive"))
      (node (ref "U7") (pin "9") (pinfunction "A4_9") (pintype "bidirectional"))
      (node (ref "U8") (pin "1") (pinfunction "~{CS}_1") (pintype "input"))
    )
    (net (code "6") (name "/GPIO1") (class "Default")
      (node (ref "BO_JP2") (pin "P$2") (pinfunction "2_P$2") (pintype "bidirectional"))
      (node (ref "BO_U1") (pin "7") (pinfunction "GPIO1_7") (pintype "output"))
    )
    (net (code "7") (name "/I_GPIO") (class "Default")
      (node (ref "JP8") (pin "2") (pinfunction "2_2") (pintype "bidirectional"))
      (node (ref "R72") (pin "1") (pinfunction "1_1") (pintype "passive"))
      (node (ref "U7") (pin "6") (pinfunction "A1_6") (pintype "bidirectional"))
    )
    (net (code "8") (name "/LI+") (class "Default")
      (node (ref "U7") (pin "28") (pinfunction "LI+_28") (pintype "power_in"))
    )
    (net (code "9") (name "/MISO") (class "Default")
      (node (ref "JP7") (pin "5") (pinfunction "5_5") (pintype "bidirectional"))
      (node (ref "U7") (pin "13") (pinfunction "MISO_13") (pintype "bidirectional"))
      (node (ref "U8") (pin "2") (pinfunction "DO_2") (pintype "output"))
    )
    (net (code "10") (name "/MOSI") (class "Default")
      (node (ref "JP7") (pin "1") (pinfunction "1_1") (pintype "bidirectional"))
      (node (ref "U7") (pin "12") (pinfunction "MOSI_12") (pintype "bidirectional"))
      (node (ref "U8") (pin "5") (pinfunction "DI_5") (pintype "input"))
    )
    (net (code "11") (name "/MUX1SC0") (class "Default")
      (node (ref "MUX1") (pin "6") (pinfunction "SC0_6") (pintype "bidirectional"))
      (node (ref "R10") (pin "1") (pinfunction "1_1") (pintype "passive"))
      (node (ref "U1") (pin "3") (pinfunction "SCK_3") (pintype "bidirectional"))
    )
    (net (code "12") (name "/MUX1SC1") (class "Default")
      (node (ref "MUX1") (pin "10") (pinfunction "SC1_10") (pintype "bidirectional"))
      (node (ref "R21") (pin "1") (pinfunction "1_1") (pintype "passive"))
      (node (ref "U2") (pin "3") (pinfunction "SCK_3") (pintype "bidirectional"))
    )
    (net (code "13") (name "/MUX1SD0") (class "Default")
      (node (ref "MUX1") (pin "5") (pinfunction "SD0_5") (pintype "bidirectional"))
      (node (ref "R9") (pin "1") (pinfunction "1_1") (pintype "passive"))
      (node (ref "U1") (pin "2") (pinfunction "SDA_2") (pintype "bidirectional"))
    )
    (net (code "14") (name "/MUX1SD1") (class "Default")
      (node (ref "MUX1") (pin "9") (pinfunction "SD1_9") (pintype "bidirectional"))
      (node (ref "R20") (pin "1") (pinfunction "1_1") (pintype "passive"))
      (node (ref "U2") (pin "2") (pinfunction "SDA_2") (pintype "bidirectional"))
    )
    (net (code "15") (name "/MUX2SC0") (class "Default")
      (node (ref "MUX2") (pin "6") (pinfunction "SC0_6") (pintype "bidirectional"))
      (node (ref "R32") (pin "1") (pinfunction "1_1") (pintype "passive"))
      (node (ref "U3") (pin "3") (pinfunction "SCK_3") (pintype "bidirectional"))
    )
    (net (code "16") (name "/MUX2SC1") (class "Default")
      (node (ref "MUX2") (pin "10") (pinfunction "SC1_10") (pintype "bidirectional"))
      (node (ref "R43") (pin "1") (pinfunction "1_1") (pintype "passive"))
      (node (ref "U4") (pin "3") (pinfunction "SCK_3") (pintype "bidirectional"))
    )
    (net (code "17") (name "/MUX2SD0") (class "Default")
      (node (ref "MUX2") (pin "5") (pinfunction "SD0_5") (pintype "bidirectional"))
      (node (ref "R31") (pin "1") (pinfunction "1_1") (pintype "passive"))
      (node (ref "U3") (pin "2") (pinfunction "SDA_2") (pintype "bidirectional"))
    )
    (net (code "18") (name "/MUX2SD1") (class "Default")
      (node (ref "MUX2") (pin "9") (pinfunction "SD1_9") (pintype "bidirectional"))
      (node (ref "R42") (pin "1") (pinfunction "1_1") (pintype "passive"))
      (node (ref "U4") (pin "2") (pinfunction "SDA_2") (pintype "bidirectional"))
    )
    (net (code "19") (name "/MUX3SC0") (class "Default")
      (node (ref "MUX3") (pin "6") (pinfunction "SC0_6") (pintype "bidirectional"))
      (node (ref "R54") (pin "1") (pinfunction "1_1") (pintype "passive"))
      (node (ref "U5") (pin "3") (pinfunction "SCK_3") (pintype "bidirectional"))
    )
    (net (code "20") (name "/MUX3SC1") (class "Default")
      (node (ref "MUX3") (pin "10") (pinfunction "SC1_10") (pintype "bidirectional"))
      (node (ref "R65") (pin "1") (pinfunction "1_1") (pintype "passive"))
      (node (ref "U6") (pin "3") (pinfunction "SCK_3") (pintype "bidirectional"))
    )
    (net (code "21") (name "/MUX3SD0") (class "Default")
      (node (ref "MUX3") (pin "5") (pinfunction "SD0_5") (pintype "bidirectional"))
      (node (ref "R53") (pin "1") (pinfunction "1_1") (pintype "passive"))
      (node (ref "U5") (pin "2") (pinfunction "SDA_2") (pintype "bidirectional"))
    )
    (net (code "22") (name "/MUX3SD1") (class "Default")
      (node (ref "MUX3") (pin "9") (pinfunction "SD1_9") (pintype "bidirectional"))
      (node (ref "R64") (pin "1") (pinfunction "1_1") (pintype "passive"))
      (node (ref "U6") (pin "2") (pinfunction "SDA_2") (pintype "bidirectional"))
    )
    (net (code "23") (name "/RST") (class "Default")
      (node (ref "R76") (pin "1") (pinfunction "1_1") (pintype "passive"))
      (node (ref "U7") (pin "8") (pinfunction "A3_8") (pintype "bidirectional"))
      (node (ref "U8") (pin "7") (pinfunction "~{RST}_7") (pintype "input"))
    )
    (net (code "24") (name "/SCL") (class "Default")
      (node (ref "JP8") (pin "4") (pinfunction "4_4") (pintype "bidirectional"))
      (node (ref "MUX1") (pin "12") (pinfunction "SCL_12") (pintype "bidirectional"))
      (node (ref "MUX2") (pin "12") (pinfunction "SCL_12") (pintype "bidirectional"))
      (node (ref "MUX3") (pin "12") (pinfunction "SCL_12") (pintype "bidirectional"))
      (node (ref "R68") (pin "1") (pinfunction "1_1") (pintype "passive"))
      (node (ref "U7") (pin "18") (pinfunction "SCL_18") (pintype "bidirectional"))
    )
    (net (code "25") (name "/SCL1") (class "Default")
      (node (ref "BO_JP1") (pin "P$3") (pinfunction "3_P$3") (pintype "bidirectional"))
      (node (ref "BO_U1") (pin "10") (pinfunction "SCL_10") (pintype "bidirectional"))
    )
    (net (code "26") (name "/SDA") (class "Default")
      (node (ref "JP8") (pin "6") (pinfunction "6_6") (pintype "bidirectional"))
      (node (ref "MUX1") (pin "13") (pinfunction "SDA_13") (pintype "bidirectional"))
      (node (ref "MUX2") (pin "13") (pinfunction "SDA_13") (pintype "bidirectional"))
      (node (ref "MUX3") (pin "13") (pinfunction "SDA_13") (pintype "bidirectional"))
      (node (ref "R67") (pin "1") (pinfunction "1_1") (pintype "passive"))
      (node (ref "U7") (pin "17") (pinfunction "SDA_17") (pintype "bidirectional"))
    )
    (net (code "27") (name "/SDA1") (class "Default")
      (node (ref "BO_JP2") (pin "P$3") (pinfunction "3_P$3") (pintype "bidirectional"))
      (node (ref "BO_U1") (pin "9") (pinfunction "SDA_9") (pintype "bidirectional"))
    )
    (net (code "28") (name "/VDD") (class "Default")
      (node (ref "BO_C1") (pin "1") (pinfunction "1_1") (pintype "passive"))
      (node (ref "BO_C2") (pin "1") (pinfunction "1_1") (pintype "passive"))
      (node (ref "BO_JP1") (pin "P$2") (pinfunction "2_P$2") (pintype "bidirectional"))
      (node (ref "BO_U1") (pin "1") (pinfunction "AVDDVCSEL_1") (pintype "power_in"))
      (node (ref "BO_U1") (pin "11") (pinfunction "AVDD_11") (pintype "power_in"))
    )
    (net (code "29") (name "/WP") (class "Default")
      (node (ref "R75") (pin "2") (pinfunction "2_2") (pintype "passive"))
      (node (ref "TP1") (pin "TP") (pinfunction "TP_TP") (pintype "input"))
      (node (ref "U8") (pin "3") (pinfunction "~{WP}_3") (pintype "input"))
    )
    (net (code "30") (name "/~{INT1}") (class "Default")
      (node (ref "MUX1") (pin "11") (pinfunction "~{INT}_11") (pintype "output"))
      (node (ref "R69") (pin "1") (pinfunction "1_1") (pintype "passive"))
      (node (ref "U7") (pin "23") (pinfunction "D6_23") (pintype "bidirectional"))
    )
    (net (code "31") (name "/~{INT2}") (class "Default")
      (node (ref "MUX2") (pin "11") (pinfunction "~{INT}_11") (pintype "output"))
      (node (ref "R73") (pin "1") (pinfunction "1_1") (pintype "passive"))
      (node (ref "U7") (pin "25") (pinfunction "D8_25") (pintype "bidirectional"))
    )
    (net (code "32") (name "/~{INT3}") (class "Default")
      (node (ref "MUX3") (pin "11") (pinfunction "~{INT}_11") (pintype "output"))
      (node (ref "R77") (pin "1") (pinfunction "1_1") (pintype "passive"))
      (node (ref "U7") (pin "20") (pinfunction "D3_20") (pintype "bidirectional"))
    )
    (net (code "33") (name "/~{I_ENABLE}") (class "Default")
      (node (ref "JP8") (pin "1") (pinfunction "1_1") (pintype "bidirectional"))
      (node (ref "R71") (pin "1") (pinfunction "1_1") (pintype "passive"))
      (node (ref "U7") (pin "5") (pinfunction "A0_5") (pintype "bidirectional"))
    )
    (net (code "34") (name "/~{MUX1INT0}") (class "Default")
      (node (ref "MUX1") (pin "4") (pinfunction "~{INT0}_4") (pintype "bidirectional"))
      (node (ref "R11") (pin "1") (pinfunction "1_1") (pintype "passive"))
      (node (ref "U1") (pin "1") (pinfunction "~{ALERT}_1") (pintype "output"))
    )
    (net (code "35") (name "/~{MUX1INT1}") (class "Default")
      (node (ref "MUX1") (pin "8") (pinfunction "~{INT1}_8") (pintype "bidirectional"))
      (node (ref "R22") (pin "1") (pinfunction "1_1") (pintype "passive"))
      (node (ref "U2") (pin "1") (pinfunction "~{ALERT}_1") (pintype "output"))
    )
    (net (code "36") (name "/~{MUX2INT0}") (class "Default")
      (node (ref "MUX2") (pin "4") (pinfunction "~{INT0}_4") (pintype "bidirectional"))
      (node (ref "R33") (pin "1") (pinfunction "1_1") (pintype "passive"))
      (node (ref "U3") (pin "1") (pinfunction "~{ALERT}_1") (pintype "output"))
    )
    (net (code "37") (name "/~{MUX2INT1}") (class "Default")
      (node (ref "MUX2") (pin "8") (pinfunction "~{INT1}_8") (pintype "bidirectional"))
      (node (ref "R44") (pin "1") (pinfunction "1_1") (pintype "passive"))
      (node (ref "U4") (pin "1") (pinfunction "~{ALERT}_1") (pintype "output"))
    )
    (net (code "38") (name "/~{MUX3INT0}") (class "Default")
      (node (ref "MUX3") (pin "4") (pinfunction "~{INT0}_4") (pintype "bidirectional"))
      (node (ref "R55") (pin "1") (pinfunction "1_1") (pintype "passive"))
      (node (ref "U5") (pin "1") (pinfunction "~{ALERT}_1") (pintype "output"))
    )
    (net (code "39") (name "/~{MUX3INT1}") (class "Default")
      (node (ref "MUX3") (pin "8") (pinfunction "~{INT1}_8") (pintype "bidirectional"))
      (node (ref "R66") (pin "1") (pinfunction "1_1") (pintype "passive"))
      (node (ref "U6") (pin "1") (pinfunction "~{ALERT}_1") (pintype "output"))
    )
    (net (code "40") (name "/~{RST1}") (class "Default")
      (node (ref "MUX1") (pin "3") (pinfunction "~{RESET}_3") (pintype "input"))
      (node (ref "R70") (pin "1") (pinfunction "1_1") (pintype "passive"))
      (node (ref "U7") (pin "22") (pinfunction "D5_22") (pintype "bidirectional"))
    )
    (net (code "41") (name "/~{RST2}") (class "Default")
      (node (ref "MUX2") (pin "3") (pinfunction "~{RESET}_3") (pintype "input"))
      (node (ref "R74") (pin "1") (pinfunction "1_1") (pintype "passive"))
      (node (ref "U7") (pin "24") (pinfunction "D7_24") (pintype "bidirectional"))
    )
    (net (code "42") (name "/~{RST3}") (class "Default")
      (node (ref "MUX3") (pin "3") (pinfunction "~{RESET}_3") (pintype "input"))
      (node (ref "R78") (pin "1") (pinfunction "1_1") (pintype "passive"))
      (node (ref "U7") (pin "21") (pinfunction "D4_21") (pintype "bidirectional"))
    )
    (net (code "43") (name "/~{XSHUT1}") (class "Default")
      (node (ref "BO_JP2") (pin "P$1") (pinfunction "1_P$1") (pintype "bidirectional"))
      (node (ref "BO_U1") (pin "5") (pinfunction "XSHUT_5") (pintype "input"))
    )
    (net (code "44") (name "GND") (class "Default")
      (node (ref "BO_C1") (pin "2") (pinfunction "2_2") (pintype "passive"))
      (node (ref "BO_C2") (pin "2") (pinfunction "2_2") (pintype "passive"))
      (node (ref "BO_JP1") (pin "P$1") (pinfunction "1_P$1") (pintype "bidirectional"))
      (node (ref "BO_U1") (pin "12") (pinfunction "GND_12") (pintype "power_in"))
      (node (ref "BO_U1") (pin "2") (pinfunction "AVSSVCSEL_2") (pintype "power_in"))
      (node (ref "BO_U1") (pin "3") (pinfunction "GND_3") (pintype "power_in"))
      (node (ref "BO_U1") (pin "4") (pinfunction "GND_4") (pintype "power_in"))
      (node (ref "BO_U1") (pin "6") (pinfunction "GND_6") (pintype "power_in"))
      (node (ref "C1") (pin "2") (pinfunction "2_2") (pintype "passive"))
      (node (ref "C10") (pin "2") (pinfunction "2_2") (pintype "passive"))
      (node (ref "C11") (pin "2") (pinfunction "2_2") (pintype "passive"))
      (node (ref "C12") (pin "2") (pinfunction "2_2") (pintype "passive"))
      (node (ref "C13") (pin "2") (pinfunction "2_2") (pintype "passive"))
      (node (ref "C14") (pin "2") (pinfunction "2_2") (pintype "passive"))
      (node (ref "C15") (pin "2") (pinfunction "2_2") (pintype "passive"))
      (node (ref "C16") (pin "2") (pinfunction "2_2") (pintype "passive"))
      (node (ref "C17") (pin "2") (pinfunction "2_2") (pintype "passive"))
      (node (ref "C18") (pin "2") (pinfunction "2_2") (pintype "passive"))
      (node (ref "C19") (pin "C") (pinfunction "-_C") (pintype "passive"))
      (node (ref "C2") (pin "2") (pinfunction "2_2") (pintype "passive"))
      (node (ref "C20") (pin "C") (pinfunction "-_C") (pintype "passive"))
      (node (ref "C21") (pin "C") (pinfunction "-_C") (pintype "passive"))
      (node (ref "C22") (pin "C") (pinfunction "-_C") (pintype "passive"))
      (node (ref "C23") (pin "C") (pinfunction "-_C") (pintype "passive"))
      (node (ref "C24") (pin "C") (pinfunction "-_C") (pintype "passive"))
      (node (ref "C25") (pin "C") (pinfunction "-_C") (pintype "passive"))
      (node (ref "C26") (pin "2") (pinfunction "2_2") (pintype "passive"))
      (node (ref "C28") (pin "2") (pinfunction "2_2") (pintype "passive"))
      (node (ref "C29") (pin "2") (pinfunction "2_2") (pintype "passive"))
      (node (ref "C3") (pin "2") (pinfunction "2_2") (pintype "passive"))
      (node (ref "C30") (pin "2") (pinfunction "2_2") (pintype "passive"))
      (node (ref "C31") (pin "2") (pinfunction "2_2") (pintype "passive"))
      (node (ref "C33") (pin "2") (pinfunction "2_2") (pintype "passive"))
      (node (ref "C34") (pin "2") (pinfunction "2_2") (pintype "passive"))
      (node (ref "C4") (pin "2") (pinfunction "2_2") (pintype "passive"))
      (node (ref "C5") (pin "2") (pinfunction "2_2") (pintype "passive"))
      (node (ref "C6") (pin "2") (pinfunction "2_2") (pintype "passive"))
      (node (ref "C7") (pin "2") (pinfunction "2_2") (pintype "passive"))
      (node (ref "C8") (pin "2") (pinfunction "2_2") (pintype "passive"))
      (node (ref "C9") (pin "2") (pinfunction "2_2") (pintype "passive"))
      (node (ref "JP1") (pin "10") (pinfunction "10_10") (pintype "bidirectional"))
      (node (ref "JP10") (pin "1") (pinfunction "1_1") (pintype "bidirectional"))
      (node (ref "JP10") (pin "2") (pinfunction "2_2") (pintype "bidirectional"))
      (node (ref "JP10") (pin "3") (pinfunction "3_3") (pintype "bidirectional"))
      (node (ref "JP10") (pin "4") (pinfunction "4_4") (pintype "bidirectional"))
      (node (ref "JP10") (pin "5") (pinfunction "5_5") (pintype "bidirectional"))
      (node (ref "JP10") (pin "6") (pinfunction "6_6") (pintype "bidirectional"))
      (node (ref "JP2") (pin "10") (pinfunction "10_10") (pintype "bidirectional"))
      (node (ref "JP3") (pin "10") (pinfunction "10_10") (pintype "bidirectional"))
      (node (ref "JP4") (pin "10") (pinfunction "10_10") (pintype "bidirectional"))
      (node (ref "JP5") (pin "10") (pinfunction "10_10") (pintype "bidirectional"))
      (node (ref "JP6") (pin "10") (pinfunction "10_10") (pintype "bidirectional"))
      (node (ref "JP7") (pin "4") (pinfunction "4_4") (pintype "bidirectional"))
      (node (ref "JP8") (pin "3") (pinfunction "3_3") (pintype "bidirectional"))
      (node (ref "JP9") (pin "1") (pinfunction "1_1") (pintype "bidirectional"))
      (node (ref "JP9") (pin "2") (pinfunction "2_2") (pintype "bidirectional"))
      (node (ref "JP9") (pin "3") (pinfunction "3_3") (pintype "bidirectional"))
      (node (ref "JP9") (pin "4") (pinfunction "4_4") (pintype "bidirectional"))
      (node (ref "JP9") (pin "5") (pinfunction "5_5") (pintype "bidirectional"))
      (node (ref "JP9") (pin "6") (pinfunction "6_6") (pintype "bidirectional"))
      (node (ref "LED1") (pin "3-GND") (pinfunction "GND_3-GND") (pintype "power_in"))
      (node (ref "LED10") (pin "3-GND") (pinfunction "GND_3-GND") (pintype "power_in"))
      (node (ref "LED11") (pin "3-GND") (pinfunction "GND_3-GND") (pintype "power_in"))
      (node (ref "LED12") (pin "3-GND") (pinfunction "GND_3-GND") (pintype "power_in"))
      (node (ref "LED13") (pin "3-GND") (pinfunction "GND_3-GND") (pintype "power_in"))
      (node (ref "LED14") (pin "3-GND") (pinfunction "GND_3-GND") (pintype "power_in"))
      (node (ref "LED15") (pin "3-GND") (pinfunction "GND_3-GND") (pintype "power_in"))
      (node (ref "LED16") (pin "3-GND") (pinfunction "GND_3-GND") (pintype "power_in"))
      (node (ref "LED17") (pin "3-GND") (pinfunction "GND_3-GND") (pintype "power_in"))
      (node (ref "LED18") (pin "3-GND") (pinfunction "GND_3-GND") (pintype "power_in"))
      (node (ref "LED19") (pin "3-GND") (pinfunction "GND_3-GND") (pintype "power_in"))
      (node (ref "LED2") (pin "3-GND") (pinfunction "GND_3-GND") (pintype "power_in"))
      (node (ref "LED20") (pin "3-GND") (pinfunction "GND_3-GND") (pintype "power_in"))
      (node (ref "LED21") (pin "3-GND") (pinfunction "GND_3-GND") (pintype "power_in"))
      (node (ref "LED22") (pin "3-GND") (pinfunction "GND_3-GND") (pintype "power_in"))
      (node (ref "LED23") (pin "3-GND") (pinfunction "GND_3-GND") (pintype "power_in"))
      (node (ref "LED24") (pin "3-GND") (pinfunction "GND_3-GND") (pintype "power_in"))
      (node (ref "LED25") (pin "3-GND") (pinfunction "GND_3-GND") (pintype "power_in"))
      (node (ref "LED26") (pin "3-GND") (pinfunction "GND_3-GND") (pintype "power_in"))
      (node (ref "LED27") (pin "3-GND") (pinfunction "GND_3-GND") (pintype "power_in"))
      (node (ref "LED28") (pin "3-GND") (pinfunction "GND_3-GND") (pintype "power_in"))
      (node (ref "LED29") (pin "3-GND") (pinfunction "GND_3-GND") (pintype "power_in"))
      (node (ref "LED3") (pin "3-GND") (pinfunction "GND_3-GND") (pintype "power_in"))
      (node (ref "LED30") (pin "3-GND") (pinfunction "GND_3-GND") (pintype "power_in"))
      (node (ref "LED31") (pin "3-GND") (pinfunction "GND_3-GND") (pintype "power_in"))
      (node (ref "LED32") (pin "3-GND") (pinfunction "GND_3-GND") (pintype "power_in"))
      (node (ref "LED33") (pin "3-GND") (pinfunction "GND_3-GND") (pintype "power_in"))
      (node (ref "LED34") (pin "3-GND") (pinfunction "GND_3-GND") (pintype "power_in"))
      (node (ref "LED35") (pin "3-GND") (pinfunction "GND_3-GND") (pintype "power_in"))
      (node (ref "LED36") (pin "3-GND") (pinfunction "GND_3-GND") (pintype "power_in"))
      (node (ref "LED37") (pin "3-GND") (pinfunction "GND_3-GND") (pintype "power_in"))
      (node (ref "LED38") (pin "3-GND") (pinfunction "GND_3-GND") (pintype "power_in"))
      (node (ref "LED39") (pin "3-GND") (pinfunction "GND_3-GND") (pintype "power_in"))
      (node (ref "LED4") (pin "3-GND") (pinfunction "GND_3-GND") (pintype "power_in"))
      (node (ref "LED40") (pin "3-GND") (pinfunction "GND_3-GND") (pintype "power_in"))
      (node (ref "LED41") (pin "3-GND") (pinfunction "GND_3-GND") (pintype "power_in"))
      (node (ref "LED42") (pin "3-GND") (pinfunction "GND_3-GND") (pintype "power_in"))
      (node (ref "LED43") (pin "3-GND") (pinfunction "GND_3-GND") (pintype "power_in"))
      (node (ref "LED44") (pin "3-GND") (pinfunction "GND_3-GND") (pintype "power_in"))
      (node (ref "LED45") (pin "3-GND") (pinfunction "GND_3-GND") (pintype "power_in"))
      (node (ref "LED46") (pin "3-GND") (pinfunction "GND_3-GND") (pintype "power_in"))
      (node (ref "LED47") (pin "3-GND") (pinfunction "GND_3-GND") (pintype "power_in"))
      (node (ref "LED48") (pin "3-GND") (pinfunction "GND_3-GND") (pintype "power_in"))
      (node (ref "LED49") (pin "3-GND") (pinfunction "GND_3-GND") (pintype "power_in"))
      (node (ref "LED5") (pin "3-GND") (pinfunction "GND_3-GND") (pintype "power_in"))
      (node (ref "LED50") (pin "3-GND") (pinfunction "GND_3-GND") (pintype "power_in"))
      (node (ref "LED51") (pin "3-GND") (pinfunction "GND_3-GND") (pintype "power_in"))
      (node (ref "LED52") (pin "3-GND") (pinfunction "GND_3-GND") (pintype "power_in"))
      (node (ref "LED53") (pin "3-GND") (pinfunction "GND_3-GND") (pintype "power_in"))
      (node (ref "LED54") (pin "3-GND") (pinfunction "GND_3-GND") (pintype "power_in"))
      (node (ref "LED55") (pin "3-GND") (pinfunction "GND_3-GND") (pintype "power_in"))
      (node (ref "LED6") (pin "3-GND") (pinfunction "GND_3-GND") (pintype "power_in"))
      (node (ref "LED7") (pin "3-GND") (pinfunction "GND_3-GND") (pintype "power_in"))
      (node (ref "LED8") (pin "3-GND") (pinfunction "GND_3-GND") (pintype "power_in"))
      (node (ref "LED9") (pin "3-GND") (pinfunction "GND_3-GND") (pintype "power_in"))
      (node (ref "MUX1") (pin "1") (pinfunction "A0_1") (pintype "input"))
      (node (ref "MUX1") (pin "2") (pinfunction "A1_2") (pintype "input"))
      (node (ref "MUX1") (pin "7") (pinfunction "GND_7") (pintype "power_in"))
      (node (ref "MUX2") (pin "2") (pinfunction "A1_2") (pintype "input"))
      (node (ref "MUX2") (pin "7") (pinfunction "GND_7") (pintype "power_in"))
      (node (ref "MUX3") (pin "1") (pinfunction "A0_1") (pintype "input"))
      (node (ref "MUX3") (pin "7") (pinfunction "GND_7") (pintype "power_in"))
      (node (ref "P1") (pin "RING") (pinfunction "RING_RING") (pintype "bidirectional"))
      (node (ref "P1") (pin "RING_SW") (pinfunction "RING_SW_RING_SW") (pintype "bidirectional"))
      (node (ref "R75") (pin "1") (pinfunction "1_1") (pintype "passive"))
      (node (ref "R81") (pin "1") (pinfunction "1_1") (pintype "passive"))
      (node (ref "U1") (pin "5") (pinfunction "GND_5") (pintype "power_in"))
      (node (ref "U1") (pin "6") (pinfunction "GND_6") (pintype "power_in"))
      (node (ref "U1") (pin "7") (pinfunction "GND_7") (pintype "power_in"))
      (node (ref "U1") (pin "8") (pinfunction "GND_8") (pintype "power_in"))
      (node (ref "U1") (pin "PAD") (pinfunction "GND_PAD") (pintype "power_in"))
      (node (ref "U2") (pin "5") (pinfunction "GND_5") (pintype "power_in"))
      (node (ref "U2") (pin "6") (pinfunction "GND_6") (pintype "power_in"))
      (node (ref "U2") (pin "7") (pinfunction "GND_7") (pintype "power_in"))
      (node (ref "U2") (pin "8") (pinfunction "GND_8") (pintype "power_in"))
      (node (ref "U2") (pin "PAD") (pinfunction "GND_PAD") (pintype "power_in"))
      (node (ref "U3") (pin "5") (pinfunction "GND_5") (pintype "power_in"))
      (node (ref "U3") (pin "6") (pinfunction "GND_6") (pintype "power_in"))
      (node (ref "U3") (pin "7") (pinfunction "GND_7") (pintype "power_in"))
      (node (ref "U3") (pin "8") (pinfunction "GND_8") (pintype "power_in"))
      (node (ref "U3") (pin "PAD") (pinfunction "GND_PAD") (pintype "power_in"))
      (node (ref "U4") (pin "5") (pinfunction "GND_5") (pintype "power_in"))
      (node (ref "U4") (pin "6") (pinfunction "GND_6") (pintype "power_in"))
      (node (ref "U4") (pin "7") (pinfunction "GND_7") (pintype "power_in"))
      (node (ref "U4") (pin "8") (pinfunction "GND_8") (pintype "power_in"))
      (node (ref "U4") (pin "PAD") (pinfunction "GND_PAD") (pintype "power_in"))
      (node (ref "U5") (pin "5") (pinfunction "GND_5") (pintype "power_in"))
      (node (ref "U5") (pin "6") (pinfunction "GND_6") (pintype "power_in"))
      (node (ref "U5") (pin "7") (pinfunction "GND_7") (pintype "power_in"))
      (node (ref "U5") (pin "8") (pinfunction "GND_8") (pintype "power_in"))
      (node (ref "U5") (pin "PAD") (pinfunction "GND_PAD") (pintype "power_in"))
      (node (ref "U6") (pin "5") (pinfunction "GND_5") (pintype "power_in"))
      (node (ref "U6") (pin "6") (pinfunction "GND_6") (pintype "power_in"))
      (node (ref "U6") (pin "7") (pinfunction "GND_7") (pintype "power_in"))
      (node (ref "U6") (pin "8") (pinfunction "GND_8") (pintype "power_in"))
      (node (ref "U6") (pin "PAD") (pinfunction "GND_PAD") (pintype "power_in"))
      (node (ref "U7") (pin "4") (pinfunction "GND_4") (pintype "power_in"))
      (node (ref "U8") (pin "4") (pinfunction "GND_4") (pintype "power_in"))
      (node (ref "U9") (pin "3") (pinfunction "GND_3") (pintype "power_in"))
    )
    (net (code "45") (name "NP_DI") (class "Default")
      (node (ref "LED49") (pin "4-DIN") (pinfunction "DI_4-DIN") (pintype "input"))
      (node (ref "U7") (pin "7") (pinfunction "A2_7") (pintype "bidirectional"))
    )
    (net (code "46") (name "Net-(C32-Pad2)") (class "Default")
      (node (ref "C32") (pin "2") (pinfunction "2_2") (pintype "passive"))
      (node (ref "R80") (pin "1") (pinfunction "1_1") (pintype "passive"))
      (node (ref "R81") (pin "2") (pinfunction "2_2") (pintype "passive"))
      (node (ref "R82") (pin "1") (pinfunction "1_1") (pintype "passive"))
    )
    (net (code "47") (name "Net-(D1-A)") (class "Default")
      (node (ref "D1") (pin "ANODE") (pinfunction "A_ANODE") (pintype "bidirectional"))
      (node (ref "P1") (pin "TIP") (pinfunction "TIP_TIP") (pintype "bidirectional"))
    )
    (net (code "48") (name "Net-(JP1-Pad2)") (class "Default")
      (node (ref "JP1") (pin "2") (pinfunction "2_2") (pintype "bidirectional"))
      (node (ref "R1") (pin "2") (pinfunction "2_2") (pintype "passive"))
    )
    (net (code "49") (name "Net-(JP1-Pad3)") (class "Default")
      (node (ref "JP1") (pin "3") (pinfunction "3_3") (pintype "bidirectional"))
      (node (ref "R2") (pin "2") (pinfunction "2_2") (pintype "passive"))
    )
    (net (code "50") (name "Net-(JP1-Pad4)") (class "Default")
      (node (ref "JP1") (pin "4") (pinfunction "4_4") (pintype "bidirectional"))
      (node (ref "R3") (pin "2") (pinfunction "2_2") (pintype "passive"))
    )
    (net (code "51") (name "Net-(JP1-Pad5)") (class "Default")
      (node (ref "JP1") (pin "5") (pinfunction "5_5") (pintype "bidirectional"))
      (node (ref "R4") (pin "2") (pinfunction "2_2") (pintype "passive"))
    )
    (net (code "52") (name "Net-(JP1-Pad6)") (class "Default")
      (node (ref "JP1") (pin "6") (pinfunction "6_6") (pintype "bidirectional"))
      (node (ref "R5") (pin "2") (pinfunction "2_2") (pintype "passive"))
    )
    (net (code "53") (name "Net-(JP1-Pad7)") (class "Default")
      (node (ref "JP1") (pin "7") (pinfunction "7_7") (pintype "bidirectional"))
      (node (ref "R6") (pin "2") (pinfunction "2_2") (pintype "passive"))
    )
    (net (code "54") (name "Net-(JP1-Pad8)") (class "Default")
      (node (ref "JP1") (pin "8") (pinfunction "8_8") (pintype "bidirectional"))
      (node (ref "R7") (pin "2") (pinfunction "2_2") (pintype "passive"))
    )
    (net (code "55") (name "Net-(JP1-Pad9)") (class "Default")
      (node (ref "JP1") (pin "9") (pinfunction "9_9") (pintype "bidirectional"))
      (node (ref "R8") (pin "2") (pinfunction "2_2") (pintype "passive"))
    )
    (net (code "56") (name "Net-(JP2-Pad2)") (class "Default")
      (node (ref "JP2") (pin "2") (pinfunction "2_2") (pintype "bidirectional"))
      (node (ref "R12") (pin "2") (pinfunction "2_2") (pintype "passive"))
    )
    (net (code "57") (name "Net-(JP2-Pad3)") (class "Default")
      (node (ref "JP2") (pin "3") (pinfunction "3_3") (pintype "bidirectional"))
      (node (ref "R13") (pin "2") (pinfunction "2_2") (pintype "passive"))
    )
    (net (code "58") (name "Net-(JP2-Pad4)") (class "Default")
      (node (ref "JP2") (pin "4") (pinfunction "4_4") (pintype "bidirectional"))
      (node (ref "R14") (pin "2") (pinfunction "2_2") (pintype "passive"))
    )
    (net (code "59") (name "Net-(JP2-Pad5)") (class "Default")
      (node (ref "JP2") (pin "5") (pinfunction "5_5") (pintype "bidirectional"))
      (node (ref "R15") (pin "2") (pinfunction "2_2") (pintype "passive"))
    )
    (net (code "60") (name "Net-(JP2-Pad6)") (class "Default")
      (node (ref "JP2") (pin "6") (pinfunction "6_6") (pintype "bidirectional"))
      (node (ref "R16") (pin "2") (pinfunction "2_2") (pintype "passive"))
    )
    (net (code "61") (name "Net-(JP2-Pad7)") (class "Default")
      (node (ref "JP2") (pin "7") (pinfunction "7_7") (pintype "bidirectional"))
      (node (ref "R17") (pin "2") (pinfunction "2_2") (pintype "passive"))
    )
    (net (code "62") (name "Net-(JP2-Pad8)") (class "Default")
      (node (ref "JP2") (pin "8") (pinfunction "8_8") (pintype "bidirectional"))
      (node (ref "R18") (pin "2") (pinfunction "2_2") (pintype "passive"))
    )
    (net (code "63") (name "Net-(JP2-Pad9)") (class "Default")
      (node (ref "JP2") (pin "9") (pinfunction "9_9") (pintype "bidirectional"))
      (node (ref "R19") (pin "2") (pinfunction "2_2") (pintype "passive"))
    )
    (net (code "64") (name "Net-(JP3-Pad2)") (class "Default")
      (node (ref "JP3") (pin "2") (pinfunction "2_2") (pintype "bidirectional"))
      (node (ref "R23") (pin "2") (pinfunction "2_2") (pintype "passive"))
    )
    (net (code "65") (name "Net-(JP3-Pad3)") (class "Default")
      (node (ref "JP3") (pin "3") (pinfunction "3_3") (pintype "bidirectional"))
      (node (ref "R24") (pin "2") (pinfunction "2_2") (pintype "passive"))
    )
    (net (code "66") (name "Net-(JP3-Pad4)") (class "Default")
      (node (ref "JP3") (pin "4") (pinfunction "4_4") (pintype "bidirectional"))
      (node (ref "R25") (pin "2") (pinfunction "2_2") (pintype "passive"))
    )
    (net (code "67") (name "Net-(JP3-Pad5)") (class "Default")
      (node (ref "JP3") (pin "5") (pinfunction "5_5") (pintype "bidirectional"))
      (node (ref "R26") (pin "2") (pinfunction "2_2") (pintype "passive"))
    )
    (net (code "68") (name "Net-(JP3-Pad6)") (class "Default")
      (node (ref "JP3") (pin "6") (pinfunction "6_6") (pintype "bidirectional"))
      (node (ref "R27") (pin "2") (pinfunction "2_2") (pintype "passive"))
    )
    (net (code "69") (name "Net-(JP3-Pad7)") (class "Default")
      (node (ref "JP3") (pin "7") (pinfunction "7_7") (pintype "bidirectional"))
      (node (ref "R28") (pin "2") (pinfunction "2_2") (pintype "passive"))
    )
    (net (code "70") (name "Net-(JP3-Pad8)") (class "Default")
      (node (ref "JP3") (pin "8") (pinfunction "8_8") (pintype "bidirectional"))
      (node (ref "R29") (pin "2") (pinfunction "2_2") (pintype "passive"))
    )
    (net (code "71") (name "Net-(JP3-Pad9)") (class "Default")
      (node (ref "JP3") (pin "9") (pinfunction "9_9") (pintype "bidirectional"))
      (node (ref "R30") (pin "2") (pinfunction "2_2") (pintype "passive"))
    )
    (net (code "72") (name "Net-(JP4-Pad2)") (class "Default")
      (node (ref "JP4") (pin "2") (pinfunction "2_2") (pintype "bidirectional"))
      (node (ref "R34") (pin "2") (pinfunction "2_2") (pintype "passive"))
    )
    (net (code "73") (name "Net-(JP4-Pad3)") (class "Default")
      (node (ref "JP4") (pin "3") (pinfunction "3_3") (pintype "bidirectional"))
      (node (ref "R35") (pin "2") (pinfunction "2_2") (pintype "passive"))
    )
    (net (code "74") (name "Net-(JP4-Pad4)") (class "Default")
      (node (ref "JP4") (pin "4") (pinfunction "4_4") (pintype "bidirectional"))
      (node (ref "R36") (pin "2") (pinfunction "2_2") (pintype "passive"))
    )
    (net (code "75") (name "Net-(JP4-Pad5)") (class "Default")
      (node (ref "JP4") (pin "5") (pinfunction "5_5") (pintype "bidirectional"))
      (node (ref "R37") (pin "2") (pinfunction "2_2") (pintype "passive"))
    )
    (net (code "76") (name "Net-(JP4-Pad6)") (class "Default")
      (node (ref "JP4") (pin "6") (pinfunction "6_6") (pintype "bidirectional"))
      (node (ref "R38") (pin "2") (pinfunction "2_2") (pintype "passive"))
    )
    (net (code "77") (name "Net-(JP4-Pad7)") (class "Default")
      (node (ref "JP4") (pin "7") (pinfunction "7_7") (pintype "bidirectional"))
      (node (ref "R39") (pin "2") (pinfunction "2_2") (pintype "passive"))
    )
    (net (code "78") (name "Net-(JP4-Pad8)") (class "Default")
      (node (ref "JP4") (pin "8") (pinfunction "8_8") (pintype "bidirectional"))
      (node (ref "R40") (pin "2") (pinfunction "2_2") (pintype "passive"))
    )
    (net (code "79") (name "Net-(JP4-Pad9)") (class "Default")
      (node (ref "JP4") (pin "9") (pinfunction "9_9") (pintype "bidirectional"))
      (node (ref "R41") (pin "2") (pinfunction "2_2") (pintype "passive"))
    )
    (net (code "80") (name "Net-(JP5-Pad2)") (class "Default")
      (node (ref "JP5") (pin "2") (pinfunction "2_2") (pintype "bidirectional"))
      (node (ref "R45") (pin "2") (pinfunction "2_2") (pintype "passive"))
    )
    (net (code "81") (name "Net-(JP5-Pad3)") (class "Default")
      (node (ref "JP5") (pin "3") (pinfunction "3_3") (pintype "bidirectional"))
      (node (ref "R46") (pin "2") (pinfunction "2_2") (pintype "passive"))
    )
    (net (code "82") (name "Net-(JP5-Pad4)") (class "Default")
      (node (ref "JP5") (pin "4") (pinfunction "4_4") (pintype "bidirectional"))
      (node (ref "R47") (pin "2") (pinfunction "2_2") (pintype "passive"))
    )
    (net (code "83") (name "Net-(JP5-Pad5)") (class "Default")
      (node (ref "JP5") (pin "5") (pinfunction "5_5") (pintype "bidirectional"))
      (node (ref "R48") (pin "2") (pinfunction "2_2") (pintype "passive"))
    )
    (net (code "84") (name "Net-(JP5-Pad6)") (class "Default")
      (node (ref "JP5") (pin "6") (pinfunction "6_6") (pintype "bidirectional"))
      (node (ref "R49") (pin "2") (pinfunction "2_2") (pintype "passive"))
    )
    (net (code "85") (name "Net-(JP5-Pad7)") (class "Default")
      (node (ref "JP5") (pin "7") (pinfunction "7_7") (pintype "bidirectional"))
      (node (ref "R50") (pin "2") (pinfunction "2_2") (pintype "passive"))
    )
    (net (code "86") (name "Net-(JP5-Pad8)") (class "Default")
      (node (ref "JP5") (pin "8") (pinfunction "8_8") (pintype "bidirectional"))
      (node (ref "R51") (pin "2") (pinfunction "2_2") (pintype "passive"))
    )
    (net (code "87") (name "Net-(JP5-Pad9)") (class "Default")
      (node (ref "JP5") (pin "9") (pinfunction "9_9") (pintype "bidirectional"))
      (node (ref "R52") (pin "2") (pinfunction "2_2") (pintype "passive"))
    )
    (net (code "88") (name "Net-(JP6-Pad2)") (class "Default")
      (node (ref "JP6") (pin "2") (pinfunction "2_2") (pintype "bidirectional"))
      (node (ref "R56") (pin "2") (pinfunction "2_2") (pintype "passive"))
    )
    (net (code "89") (name "Net-(JP6-Pad3)") (class "Default")
      (node (ref "JP6") (pin "3") (pinfunction "3_3") (pintype "bidirectional"))
      (node (ref "R57") (pin "2") (pinfunction "2_2") (pintype "passive"))
    )
    (net (code "90") (name "Net-(JP6-Pad4)") (class "Default")
      (node (ref "JP6") (pin "4") (pinfunction "4_4") (pintype "bidirectional"))
      (node (ref "R58") (pin "2") (pinfunction "2_2") (pintype "passive"))
    )
    (net (code "91") (name "Net-(JP6-Pad5)") (class "Default")
      (node (ref "JP6") (pin "5") (pinfunction "5_5") (pintype "bidirectional"))
      (node (ref "R59") (pin "2") (pinfunction "2_2") (pintype "passive"))
    )
    (net (code "92") (name "Net-(JP6-Pad6)") (class "Default")
      (node (ref "JP6") (pin "6") (pinfunction "6_6") (pintype "bidirectional"))
      (node (ref "R60") (pin "2") (pinfunction "2_2") (pintype "passive"))
    )
    (net (code "93") (name "Net-(JP6-Pad7)") (class "Default")
      (node (ref "JP6") (pin "7") (pinfunction "7_7") (pintype "bidirectional"))
      (node (ref "R61") (pin "2") (pinfunction "2_2") (pintype "passive"))
    )
    (net (code "94") (name "Net-(JP6-Pad8)") (class "Default")
      (node (ref "JP6") (pin "8") (pinfunction "8_8") (pintype "bidirectional"))
      (node (ref "R62") (pin "2") (pinfunction "2_2") (pintype "passive"))
    )
    (net (code "95") (name "Net-(JP6-Pad9)") (class "Default")
      (node (ref "JP6") (pin "9") (pinfunction "9_9") (pintype "bidirectional"))
      (node (ref "R63") (pin "2") (pinfunction "2_2") (pintype "passive"))
    )
    (net (code "96") (name "Net-(LED1-DI)") (class "Default")
      (node (ref "LED1") (pin "4-DIN") (pinfunction "DI_4-DIN") (pintype "input"))
      (node (ref "LED55") (pin "2-DOUT") (pinfunction "DO_2-DOUT") (pintype "output"))
    )
    (net (code "97") (name "Net-(LED1-DO)") (class "Default")
      (node (ref "LED1") (pin "2-DOUT") (pinfunction "DO_2-DOUT") (pintype "output"))
      (node (ref "LED2") (pin "4-DIN") (pinfunction "DI_4-DIN") (pintype "input"))
    )
    (net (code "98") (name "Net-(LED2-DO)") (class "Default")
      (node (ref "LED2") (pin "2-DOUT") (pinfunction "DO_2-DOUT") (pintype "output"))
      (node (ref "LED3") (pin "4-DIN") (pinfunction "DI_4-DIN") (pintype "input"))
    )
    (net (code "99") (name "Net-(LED3-DO)") (class "Default")
      (node (ref "LED3") (pin "2-DOUT") (pinfunction "DO_2-DOUT") (pintype "output"))
      (node (ref "LED4") (pin "4-DIN") (pinfunction "DI_4-DIN") (pintype "input"))
    )
    (net (code "100") (name "Net-(LED4-DO)") (class "Default")
      (node (ref "LED4") (pin "2-DOUT") (pinfunction "DO_2-DOUT") (pintype "output"))
      (node (ref "LED5") (pin "4-DIN") (pinfunction "DI_4-DIN") (pintype "input"))
    )
    (net (code "101") (name "Net-(LED5-DO)") (class "Default")
      (node (ref "LED5") (pin "2-DOUT") (pinfunction "DO_2-DOUT") (pintype "output"))
      (node (ref "LED6") (pin "4-DIN") (pinfunction "DI_4-DIN") (pintype "input"))
    )
    (net (code "102") (name "Net-(LED6-DO)") (class "Default")
      (node (ref "LED6") (pin "2-DOUT") (pinfunction "DO_2-DOUT") (pintype "output"))
      (node (ref "LED7") (pin "4-DIN") (pinfunction "DI_4-DIN") (pintype "input"))
    )
    (net (code "103") (name "Net-(LED7-DO)") (class "Default")
      (node (ref "LED7") (pin "2-DOUT") (pinfunction "DO_2-DOUT") (pintype "output"))
      (node (ref "LED8") (pin "4-DIN") (pinfunction "DI_4-DIN") (pintype "input"))
    )
    (net (code "104") (name "Net-(LED8-DO)") (class "Default")
      (node (ref "LED8") (pin "2-DOUT") (pinfunction "DO_2-DOUT") (pintype "output"))
      (node (ref "LED9") (pin "4-DIN") (pinfunction "DI_4-DIN") (pintype "input"))
    )
    (net (code "105") (name "Net-(LED10-DI)") (class "Default")
      (node (ref "LED10") (pin "4-DIN") (pinfunction "DI_4-DIN") (pintype "input"))
      (node (ref "LED9") (pin "2-DOUT") (pinfunction "DO_2-DOUT") (pintype "output"))
    )
    (net (code "106") (name "Net-(LED10-DO)") (class "Default")
      (node (ref "LED10") (pin "2-DOUT") (pinfunction "DO_2-DOUT") (pintype "output"))
      (node (ref "LED11") (pin "4-DIN") (pinfunction "DI_4-DIN") (pintype "input"))
    )
    (net (code "107") (name "Net-(LED11-DO)") (class "Default")
      (node (ref "LED11") (pin "2-DOUT") (pinfunction "DO_2-DOUT") (pintype "output"))
      (node (ref "LED12") (pin "4-DIN") (pinfunction "DI_4-DIN") (pintype "input"))
    )
    (net (code "108") (name "Net-(LED12-DO)") (class "Default")
      (node (ref "LED12") (pin "2-DOUT") (pinfunction "DO_2-DOUT") (pintype "output"))
      (node (ref "LED13") (pin "4-DIN") (pinfunction "DI_4-DIN") (pintype "input"))
    )
    (net (code "109") (name "Net-(LED13-DO)") (class "Default")
      (node (ref "LED13") (pin "2-DOUT") (pinfunction "DO_2-DOUT") (pintype "output"))
      (node (ref "LED14") (pin "4-DIN") (pinfunction "DI_4-DIN") (pintype "input"))
    )
    (net (code "110") (name "Net-(LED14-DO)") (class "Default")
      (node (ref "LED14") (pin "2-DOUT") (pinfunction "DO_2-DOUT") (pintype "output"))
      (node (ref "LED15") (pin "4-DIN") (pinfunction "DI_4-DIN") (pintype "input"))
    )
    (net (code "111") (name "Net-(LED15-DO)") (class "Default")
      (node (ref "LED15") (pin "2-DOUT") (pinfunction "DO_2-DOUT") (pintype "output"))
      (node (ref "LED16") (pin "4-DIN") (pinfunction "DI_4-DIN") (pintype "input"))
    )
    (net (code "112") (name "Net-(LED16-DO)") (class "Default")
      (node (ref "LED16") (pin "2-DOUT") (pinfunction "DO_2-DOUT") (pintype "output"))
      (node (ref "LED17") (pin "4-DIN") (pinfunction "DI_4-DIN") (pintype "input"))
    )
    (net (code "113") (name "Net-(LED17-DO)") (class "Default")
      (node (ref "LED17") (pin "2-DOUT") (pinfunction "DO_2-DOUT") (pintype "output"))
      (node (ref "LED18") (pin "4-DIN") (pinfunction "DI_4-DIN") (pintype "input"))
    )
    (net (code "114") (name "Net-(LED18-DO)") (class "Default")
      (node (ref "LED18") (pin "2-DOUT") (pinfunction "DO_2-DOUT") (pintype "output"))
      (node (ref "LED19") (pin "4-DIN") (pinfunction "DI_4-DIN") (pintype "input"))
    )
    (net (code "115") (name "Net-(LED19-DO)") (class "Default")
      (node (ref "LED19") (pin "2-DOUT") (pinfunction "DO_2-DOUT") (pintype "output"))
      (node (ref "LED20") (pin "4-DIN") (pinfunction "DI_4-DIN") (pintype "input"))
    )
    (net (code "116") (name "Net-(LED20-DO)") (class "Default")
      (node (ref "LED20") (pin "2-DOUT") (pinfunction "DO_2-DOUT") (pintype "output"))
      (node (ref "LED21") (pin "4-DIN") (pinfunction "DI_4-DIN") (pintype "input"))
    )
    (net (code "117") (name "Net-(LED21-DO)") (class "Default")
      (node (ref "LED21") (pin "2-DOUT") (pinfunction "DO_2-DOUT") (pintype "output"))
      (node (ref "LED22") (pin "4-DIN") (pinfunction "DI_4-DIN") (pintype "input"))
    )
    (net (code "118") (name "Net-(LED22-DO)") (class "Default")
      (node (ref "LED22") (pin "2-DOUT") (pinfunction "DO_2-DOUT") (pintype "output"))
      (node (ref "LED23") (pin "4-DIN") (pinfunction "DI_4-DIN") (pintype "input"))
    )
    (net (code "119") (name "Net-(LED23-DO)") (class "Default")
      (node (ref "LED23") (pin "2-DOUT") (pinfunction "DO_2-DOUT") (pintype "output"))
      (node (ref "LED24") (pin "4-DIN") (pinfunction "DI_4-DIN") (pintype "input"))
    )
    (net (code "120") (name "Net-(LED24-DO)") (class "Default")
      (node (ref "LED24") (pin "2-DOUT") (pinfunction "DO_2-DOUT") (pintype "output"))
      (node (ref "LED25") (pin "4-DIN") (pinfunction "DI_4-DIN") (pintype "input"))
    )
    (net (code "121") (name "Net-(LED25-DO)") (class "Default")
      (node (ref "LED25") (pin "2-DOUT") (pinfunction "DO_2-DOUT") (pintype "output"))
      (node (ref "LED26") (pin "4-DIN") (pinfunction "DI_4-DIN") (pintype "input"))
    )
    (net (code "122") (name "Net-(LED26-DO)") (class "Default")
      (node (ref "LED26") (pin "2-DOUT") (pinfunction "DO_2-DOUT") (pintype "output"))
      (node (ref "LED27") (pin "4-DIN") (pinfunction "DI_4-DIN") (pintype "input"))
    )
    (net (code "123") (name "Net-(LED27-DO)") (class "Default")
      (node (ref "LED27") (pin "2-DOUT") (pinfunction "DO_2-DOUT") (pintype "output"))
      (node (ref "LED28") (pin "4-DIN") (pinfunction "DI_4-DIN") (pintype "input"))
    )
    (net (code "124") (name "Net-(LED28-DO)") (class "Default")
      (node (ref "LED28") (pin "2-DOUT") (pinfunction "DO_2-DOUT") (pintype "output"))
      (node (ref "LED29") (pin "4-DIN") (pinfunction "DI_4-DIN") (pintype "input"))
    )
    (net (code "125") (name "Net-(LED29-DO)") (class "Default")
      (node (ref "LED29") (pin "2-DOUT") (pinfunction "DO_2-DOUT") (pintype "output"))
      (node (ref "LED30") (pin "4-DIN") (pinfunction "DI_4-DIN") (pintype "input"))
    )
    (net (code "126") (name "Net-(LED30-DO)") (class "Default")
      (node (ref "LED30") (pin "2-DOUT") (pinfunction "DO_2-DOUT") (pintype "output"))
      (node (ref "LED31") (pin "4-DIN") (pinfunction "DI_4-DIN") (pintype "input"))
    )
    (net (code "127") (name "Net-(LED31-DO)") (class "Default")
      (node (ref "LED31") (pin "2-DOUT") (pinfunction "DO_2-DOUT") (pintype "output"))
      (node (ref "LED32") (pin "4-DIN") (pinfunction "DI_4-DIN") (pintype "input"))
    )
    (net (code "128") (name "Net-(LED32-DO)") (class "Default")
      (node (ref "LED32") (pin "2-DOUT") (pinfunction "DO_2-DOUT") (pintype "output"))
      (node (ref "LED33") (pin "4-DIN") (pinfunction "DI_4-DIN") (pintype "input"))
    )
    (net (code "129") (name "Net-(LED33-DO)") (class "Default")
      (node (ref "LED33") (pin "2-DOUT") (pinfunction "DO_2-DOUT") (pintype "output"))
      (node (ref "LED34") (pin "4-DIN") (pinfunction "DI_4-DIN") (pintype "input"))
    )
    (net (code "130") (name "Net-(LED34-DO)") (class "Default")
      (node (ref "LED34") (pin "2-DOUT") (pinfunction "DO_2-DOUT") (pintype "output"))
      (node (ref "LED35") (pin "4-DIN") (pinfunction "DI_4-DIN") (pintype "input"))
    )
    (net (code "131") (name "Net-(LED35-DO)") (class "Default")
      (node (ref "LED35") (pin "2-DOUT") (pinfunction "DO_2-DOUT") (pintype "output"))
      (node (ref "LED36") (pin "4-DIN") (pinfunction "DI_4-DIN") (pintype "input"))
    )
    (net (code "132") (name "Net-(LED36-DO)") (class "Default")
      (node (ref "LED36") (pin "2-DOUT") (pinfunction "DO_2-DOUT") (pintype "output"))
      (node (ref "LED37") (pin "4-DIN") (pinfunction "DI_4-DIN") (pintype "input"))
    )
    (net (code "133") (name "Net-(LED37-DO)") (class "Default")
      (node (ref "LED37") (pin "2-DOUT") (pinfunction "DO_2-DOUT") (pintype "output"))
      (node (ref "LED38") (pin "4-DIN") (pinfunction "DI_4-DIN") (pintype "input"))
    )
    (net (code "134") (name "Net-(LED38-DO)") (class "Default")
      (node (ref "LED38") (pin "2-DOUT") (pinfunction "DO_2-DOUT") (pintype "output"))
      (node (ref "LED39") (pin "4-DIN") (pinfunction "DI_4-DIN") (pintype "input"))
    )
    (net (code "135") (name "Net-(LED39-DO)") (class "Default")
      (node (ref "LED39") (pin "2-DOUT") (pinfunction "DO_2-DOUT") (pintype "output"))
      (node (ref "LED40") (pin "4-DIN") (pinfunction "DI_4-DIN") (pintype "input"))
    )
    (net (code "136") (name "Net-(LED40-DO)") (class "Default")
      (node (ref "LED40") (pin "2-DOUT") (pinfunction "DO_2-DOUT") (pintype "output"))
      (node (ref "LED41") (pin "4-DIN") (pinfunction "DI_4-DIN") (pintype "input"))
    )
    (net (code "137") (name "Net-(LED41-DO)") (class "Default")
      (node (ref "LED41") (pin "2-DOUT") (pinfunction "DO_2-DOUT") (pintype "output"))
      (node (ref "LED42") (pin "4-DIN") (pinfunction "DI_4-DIN") (pintype "input"))
    )
    (net (code "138") (name "Net-(LED42-DO)") (class "Default")
      (node (ref "LED42") (pin "2-DOUT") (pinfunction "DO_2-DOUT") (pintype "output"))
      (node (ref "LED43") (pin "4-DIN") (pinfunction "DI_4-DIN") (pintype "input"))
    )
    (net (code "139") (name "Net-(LED43-DO)") (class "Default")
      (node (ref "LED43") (pin "2-DOUT") (pinfunction "DO_2-DOUT") (pintype "output"))
      (node (ref "LED44") (pin "4-DIN") (pinfunction "DI_4-DIN") (pintype "input"))
    )
    (net (code "140") (name "Net-(LED44-DO)") (class "Default")
      (node (ref "LED44") (pin "2-DOUT") (pinfunction "DO_2-DOUT") (pintype "output"))
      (node (ref "LED45") (pin "4-DIN") (pinfunction "DI_4-DIN") (pintype "input"))
    )
    (net (code "141") (name "Net-(LED45-DO)") (class "Default")
      (node (ref "LED45") (pin "2-DOUT") (pinfunction "DO_2-DOUT") (pintype "output"))
      (node (ref "LED46") (pin "4-DIN") (pinfunction "DI_4-DIN") (pintype "input"))
    )
    (net (code "142") (name "Net-(LED46-DO)") (class "Default")
      (node (ref "LED46") (pin "2-DOUT") (pinfunction "DO_2-DOUT") (pintype "output"))
      (node (ref "LED47") (pin "4-DIN") (pinfunction "DI_4-DIN") (pintype "input"))
    )
    (net (code "143") (name "Net-(LED47-DO)") (class "Default")
      (node (ref "LED47") (pin "2-DOUT") (pinfunction "DO_2-DOUT") (pintype "output"))
      (node (ref "LED48") (pin "4-DIN") (pinfunction "DI_4-DIN") (pintype "input"))
    )
    (net (code "144") (name "Net-(LED49-DO)") (class "Default")
      (node (ref "LED49") (pin "2-DOUT") (pinfunction "DO_2-DOUT") (pintype "output"))
      (node (ref "LED50") (pin "4-DIN") (pinfunction "DI_4-DIN") (pintype "input"))
    )
    (net (code "145") (name "Net-(LED50-DO)") (class "Default")
      (node (ref "LED50") (pin "2-DOUT") (pinfunction "DO_2-DOUT") (pintype "output"))
      (node (ref "LED51") (pin "4-DIN") (pinfunction "DI_4-DIN") (pintype "input"))
    )
    (net (code "146") (name "Net-(LED51-DO)") (class "Default")
      (node (ref "LED51") (pin "2-DOUT") (pinfunction "DO_2-DOUT") (pintype "output"))
      (node (ref "LED52") (pin "4-DIN") (pinfunction "DI_4-DIN") (pintype "input"))
    )
    (net (code "147") (name "Net-(LED52-DO)") (class "Default")
      (node (ref "LED52") (pin "2-DOUT") (pinfunction "DO_2-DOUT") (pintype "output"))
      (node (ref "LED53") (pin "4-DIN") (pinfunction "DI_4-DIN") (pintype "input"))
    )
    (net (code "148") (name "Net-(LED53-DO)") (class "Default")
      (node (ref "LED53") (pin "2-DOUT") (pinfunction "DO_2-DOUT") (pintype "output"))
      (node (ref "LED54") (pin "4-DIN") (pinfunction "DI_4-DIN") (pintype "input"))
    )
    (net (code "149") (name "Net-(LED54-DO)") (class "Default")
      (node (ref "LED54") (pin "2-DOUT") (pinfunction "DO_2-DOUT") (pintype "output"))
      (node (ref "LED55") (pin "4-DIN") (pinfunction "DI_4-DIN") (pintype "input"))
    )
    (net (code "150") (name "Net-(U1-CS1)") (class "Default")
      (node (ref "R1") (pin "1") (pinfunction "1_1") (pintype "passive"))
      (node (ref "U1") (pin "16") (pinfunction "CS1_16") (pintype "input"))
    )
    (net (code "151") (name "Net-(U1-CS2)") (class "Default")
      (node (ref "R2") (pin "1") (pinfunction "1_1") (pintype "passive"))
      (node (ref "U1") (pin "15") (pinfunction "CS2_15") (pintype "input"))
    )
    (net (code "152") (name "Net-(U1-CS3)") (class "Default")
      (node (ref "R3") (pin "1") (pinfunction "1_1") (pintype "passive"))
      (node (ref "U1") (pin "14") (pinfunction "CS3_14") (pintype "input"))
    )
    (net (code "153") (name "Net-(U1-CS4)") (class "Default")
      (node (ref "R4") (pin "1") (pinfunction "1_1") (pintype "passive"))
      (node (ref "U1") (pin "13") (pinfunction "CS4_13") (pintype "input"))
    )
    (net (code "154") (name "Net-(U1-CS5)") (class "Default")
      (node (ref "R5") (pin "1") (pinfunction "1_1") (pintype "passive"))
      (node (ref "U1") (pin "12") (pinfunction "CS5_12") (pintype "input"))
    )
    (net (code "155") (name "Net-(U1-CS6)") (class "Default")
      (node (ref "R6") (pin "1") (pinfunction "1_1") (pintype "passive"))
      (node (ref "U1") (pin "11") (pinfunction "CS6_11") (pintype "input"))
    )
    (net (code "156") (name "Net-(U1-CS7)") (class "Default")
      (node (ref "R7") (pin "1") (pinfunction "1_1") (pintype "passive"))
      (node (ref "U1") (pin "10") (pinfunction "CS7_10") (pintype "input"))
    )
    (net (code "157") (name "Net-(U1-CS8)") (class "Default")
      (node (ref "R8") (pin "1") (pinfunction "1_1") (pintype "passive"))
      (node (ref "U1") (pin "9") (pinfunction "CS8_9") (pintype "input"))
    )
    (net (code "158") (name "Net-(U2-CS1)") (class "Default")
      (node (ref "R12") (pin "1") (pinfunction "1_1") (pintype "passive"))
      (node (ref "U2") (pin "16") (pinfunction "CS1_16") (pintype "input"))
    )
    (net (code "159") (name "Net-(U2-CS2)") (class "Default")
      (node (ref "R13") (pin "1") (pinfunction "1_1") (pintype "passive"))
      (node (ref "U2") (pin "15") (pinfunction "CS2_15") (pintype "input"))
    )
    (net (code "160") (name "Net-(U2-CS3)") (class "Default")
      (node (ref "R14") (pin "1") (pinfunction "1_1") (pintype "passive"))
      (node (ref "U2") (pin "14") (pinfunction "CS3_14") (pintype "input"))
    )
    (net (code "161") (name "Net-(U2-CS4)") (class "Default")
      (node (ref "R15") (pin "1") (pinfunction "1_1") (pintype "passive"))
      (node (ref "U2") (pin "13") (pinfunction "CS4_13") (pintype "input"))
    )
    (net (code "162") (name "Net-(U2-CS5)") (class "Default")
      (node (ref "R16") (pin "1") (pinfunction "1_1") (pintype "passive"))
      (node (ref "U2") (pin "12") (pinfunction "CS5_12") (pintype "input"))
    )
    (net (code "163") (name "Net-(U2-CS6)") (class "Default")
      (node (ref "R17") (pin "1") (pinfunction "1_1") (pintype "passive"))
      (node (ref "U2") (pin "11") (pinfunction "CS6_11") (pintype "input"))
    )
    (net (code "164") (name "Net-(U2-CS7)") (class "Default")
      (node (ref "R18") (pin "1") (pinfunction "1_1") (pintype "passive"))
      (node (ref "U2") (pin "10") (pinfunction "CS7_10") (pintype "input"))
    )
    (net (code "165") (name "Net-(U2-CS8)") (class "Default")
      (node (ref "R19") (pin "1") (pinfunction "1_1") (pintype "passive"))
      (node (ref "U2") (pin "9") (pinfunction "CS8_9") (pintype "input"))
    )
    (net (code "166") (name "Net-(U3-CS1)") (class "Default")
      (node (ref "R23") (pin "1") (pinfunction "1_1") (pintype "passive"))
      (node (ref "U3") (pin "16") (pinfunction "CS1_16") (pintype "input"))
    )
    (net (code "167") (name "Net-(U3-CS2)") (class "Default")
      (node (ref "R24") (pin "1") (pinfunction "1_1") (pintype "passive"))
      (node (ref "U3") (pin "15") (pinfunction "CS2_15") (pintype "input"))
    )
    (net (code "168") (name "Net-(U3-CS3)") (class "Default")
      (node (ref "R25") (pin "1") (pinfunction "1_1") (pintype "passive"))
      (node (ref "U3") (pin "14") (pinfunction "CS3_14") (pintype "input"))
    )
    (net (code "169") (name "Net-(U3-CS4)") (class "Default")
      (node (ref "R26") (pin "1") (pinfunction "1_1") (pintype "passive"))
      (node (ref "U3") (pin "13") (pinfunction "CS4_13") (pintype "input"))
    )
    (net (code "170") (name "Net-(U3-CS5)") (class "Default")
      (node (ref "R27") (pin "1") (pinfunction "1_1") (pintype "passive"))
      (node (ref "U3") (pin "12") (pinfunction "CS5_12") (pintype "input"))
    )
    (net (code "171") (name "Net-(U3-CS6)") (class "Default")
      (node (ref "R28") (pin "1") (pinfunction "1_1") (pintype "passive"))
      (node (ref "U3") (pin "11") (pinfunction "CS6_11") (pintype "input"))
    )
    (net (code "172") (name "Net-(U3-CS7)") (class "Default")
      (node (ref "R29") (pin "1") (pinfunction "1_1") (pintype "passive"))
      (node (ref "U3") (pin "10") (pinfunction "CS7_10") (pintype "input"))
    )
    (net (code "173") (name "Net-(U3-CS8)") (class "Default")
      (node (ref "R30") (pin "1") (pinfunction "1_1") (pintype "passive"))
      (node (ref "U3") (pin "9") (pinfunction "CS8_9") (pintype "input"))
    )
    (net (code "174") (name "Net-(U4-CS1)") (class "Default")
      (node (ref "R34") (pin "1") (pinfunction "1_1") (pintype "passive"))
      (node (ref "U4") (pin "16") (pinfunction "CS1_16") (pintype "input"))
    )
    (net (code "175") (name "Net-(U4-CS2)") (class "Default")
      (node (ref "R35") (pin "1") (pinfunction "1_1") (pintype "passive"))
      (node (ref "U4") (pin "15") (pinfunction "CS2_15") (pintype "input"))
    )
    (net (code "176") (name "Net-(U4-CS3)") (class "Default")
      (node (ref "R36") (pin "1") (pinfunction "1_1") (pintype "passive"))
      (node (ref "U4") (pin "14") (pinfunction "CS3_14") (pintype "input"))
    )
    (net (code "177") (name "Net-(U4-CS4)") (class "Default")
      (node (ref "R37") (pin "1") (pinfunction "1_1") (pintype "passive"))
      (node (ref "U4") (pin "13") (pinfunction "CS4_13") (pintype "input"))
    )
    (net (code "178") (name "Net-(U4-CS5)") (class "Default")
      (node (ref "R38") (pin "1") (pinfunction "1_1") (pintype "passive"))
      (node (ref "U4") (pin "12") (pinfunction "CS5_12") (pintype "input"))
    )
    (net (code "179") (name "Net-(U4-CS6)") (class "Default")
      (node (ref "R39") (pin "1") (pinfunction "1_1") (pintype "passive"))
      (node (ref "U4") (pin "11") (pinfunction "CS6_11") (pintype "input"))
    )
    (net (code "180") (name "Net-(U4-CS7)") (class "Default")
      (node (ref "R40") (pin "1") (pinfunction "1_1") (pintype "passive"))
      (node (ref "U4") (pin "10") (pinfunction "CS7_10") (pintype "input"))
    )
    (net (code "181") (name "Net-(U4-CS8)") (class "Default")
      (node (ref "R41") (pin "1") (pinfunction "1_1") (pintype "passive"))
      (node (ref "U4") (pin "9") (pinfunction "CS8_9") (pintype "input"))
    )
    (net (code "182") (name "Net-(U5-CS1)") (class "Default")
      (node (ref "R45") (pin "1") (pinfunction "1_1") (pintype "passive"))
      (node (ref "U5") (pin "16") (pinfunction "CS1_16") (pintype "input"))
    )
    (net (code "183") (name "Net-(U5-CS2)") (class "Default")
      (node (ref "R46") (pin "1") (pinfunction "1_1") (pintype "passive"))
      (node (ref "U5") (pin "15") (pinfunction "CS2_15") (pintype "input"))
    )
    (net (code "184") (name "Net-(U5-CS3)") (class "Default")
      (node (ref "R47") (pin "1") (pinfunction "1_1") (pintype "passive"))
      (node (ref "U5") (pin "14") (pinfunction "CS3_14") (pintype "input"))
    )
    (net (code "185") (name "Net-(U5-CS4)") (class "Default")
      (node (ref "R48") (pin "1") (pinfunction "1_1") (pintype "passive"))
      (node (ref "U5") (pin "13") (pinfunction "CS4_13") (pintype "input"))
    )
    (net (code "186") (name "Net-(U5-CS5)") (class "Default")
      (node (ref "R49") (pin "1") (pinfunction "1_1") (pintype "passive"))
      (node (ref "U5") (pin "12") (pinfunction "CS5_12") (pintype "input"))
    )
    (net (code "187") (name "Net-(U5-CS6)") (class "Default")
      (node (ref "R50") (pin "1") (pinfunction "1_1") (pintype "passive"))
      (node (ref "U5") (pin "11") (pinfunction "CS6_11") (pintype "input"))
    )
    (net (code "188") (name "Net-(U5-CS7)") (class "Default")
      (node (ref "R51") (pin "1") (pinfunction "1_1") (pintype "passive"))
      (node (ref "U5") (pin "10") (pinfunction "CS7_10") (pintype "input"))
    )
    (net (code "189") (name "Net-(U5-CS8)") (class "Default")
      (node (ref "R52") (pin "1") (pinfunction "1_1") (pintype "passive"))
      (node (ref "U5") (pin "9") (pinfunction "CS8_9") (pintype "input"))
    )
    (net (code "190") (name "Net-(U6-CS1)") (class "Default")
      (node (ref "R56") (pin "1") (pinfunction "1_1") (pintype "passive"))
      (node (ref "U6") (pin "16") (pinfunction "CS1_16") (pintype "input"))
    )
    (net (code "191") (name "Net-(U6-CS2)") (class "Default")
      (node (ref "R57") (pin "1") (pinfunction "1_1") (pintype "passive"))
      (node (ref "U6") (pin "15") (pinfunction "CS2_15") (pintype "input"))
    )
    (net (code "192") (name "Net-(U6-CS3)") (class "Default")
      (node (ref "R58") (pin "1") (pinfunction "1_1") (pintype "passive"))
      (node (ref "U6") (pin "14") (pinfunction "CS3_14") (pintype "input"))
    )
    (net (code "193") (name "Net-(U6-CS4)") (class "Default")
      (node (ref "R59") (pin "1") (pinfunction "1_1") (pintype "passive"))
      (node (ref "U6") (pin "13") (pinfunction "CS4_13") (pintype "input"))
    )
    (net (code "194") (name "Net-(U6-CS5)") (class "Default")
      (node (ref "R60") (pin "1") (pinfunction "1_1") (pintype "passive"))
      (node (ref "U6") (pin "12") (pinfunction "CS5_12") (pintype "input"))
    )
    (net (code "195") (name "Net-(U6-CS6)") (class "Default")
      (node (ref "R61") (pin "1") (pinfunction "1_1") (pintype "passive"))
      (node (ref "U6") (pin "11") (pinfunction "CS6_11") (pintype "input"))
    )
    (net (code "196") (name "Net-(U6-CS7)") (class "Default")
      (node (ref "R62") (pin "1") (pinfunction "1_1") (pintype "passive"))
      (node (ref "U6") (pin "10") (pinfunction "CS7_10") (pintype "input"))
    )
    (net (code "197") (name "Net-(U6-CS8)") (class "Default")
      (node (ref "R63") (pin "1") (pinfunction "1_1") (pintype "passive"))
      (node (ref "U6") (pin "9") (pinfunction "CS8_9") (pintype "input"))
    )
    (net (code "198") (name "Net-(U9-BOOT)") (class "Default")
      (node (ref "C27") (pin "1") (pinfunction "1_1") (pintype "passive"))
      (node (ref "U9") (pin "6") (pinfunction "BOOT_6") (pintype "input"))
    )
    (net (code "199") (name "Net-(U9-EN)") (class "Default")
      (node (ref "R83") (pin "1") (pinfunction "1_1") (pintype "passive"))
      (node (ref "U9") (pin "2") (pinfunction "EN_2") (pintype "input"))
    )
    (net (code "200") (name "Net-(U9-FB)") (class "Default")
      (node (ref "R82") (pin "2") (pinfunction "2_2") (pintype "passive"))
      (node (ref "U9") (pin "1") (pinfunction "FB_1") (pintype "input"))
    )
    (net (code "201") (name "Net-(U9-LX)") (class "Default")
      (node (ref "C27") (pin "2") (pinfunction "2_2") (pintype "passive"))
      (node (ref "L1") (pin "2") (pinfunction "2_2") (pintype "passive"))
      (node (ref "U9") (pin "5") (pinfunction "LX_5") (pintype "input"))
    )
    (net (code "202") (name "VIN") (class "Default")
      (node (ref "C26") (pin "1") (pinfunction "1_1") (pintype "passive"))
      (node (ref "C33") (pin "1") (pinfunction "1_1") (pintype "passive"))
      (node (ref "C34") (pin "1") (pinfunction "1_1") (pintype "passive"))
      (node (ref "D1") (pin "CATHODE") (pinfunction "C_CATHODE") (pintype "bidirectional"))
      (node (ref "R83") (pin "2") (pinfunction "2_2") (pintype "passive"))
      (node (ref "U9") (pin "4") (pinfunction "VIN_4") (pintype "power_in"))
    )
    (net (code "203") (name "unconnected-(LED48-DO-Pad2-DOUT)") (class "Default")
      (node (ref "LED48") (pin "2-DOUT") (pinfunction "DO_2-DOUT") (pintype "output"))
    )
    (net (code "204") (name "unconnected-(U7-D2-Pad19)") (class "Default")
      (node (ref "U7") (pin "19") (pinfunction "D2_19") (pintype "bidirectional"))
    )
    (net (code "205") (name "unconnected-(U7-EN-Pad27)") (class "Default")
      (node (ref "U7") (pin "27") (pinfunction "EN_27") (pintype "input"))
    )
    (net (code "206") (name "unconnected-(U7-MODE-Pad3)") (class "Default")
      (node (ref "U7") (pin "3") (pinfunction "MODE_3") (pintype "bidirectional"))
    )
    (net (code "207") (name "unconnected-(U7-NC-Pad16)") (class "Default")
      (node (ref "U7") (pin "16") (pinfunction "NC_16") (pintype "bidirectional"))
    )
    (net (code "208") (name "unconnected-(U7-RX-Pad14)") (class "Default")
      (node (ref "U7") (pin "14") (pinfunction "RX_14") (pintype "bidirectional"))
    )
    (net (code "209") (name "unconnected-(U7-TX-Pad15)") (class "Default")
      (node (ref "U7") (pin "15") (pinfunction "TX_15") (pintype "bidirectional"))
    )
    (net (code "210") (name "unconnected-(U7-~{RST}-Pad1)") (class "Default")
      (node (ref "U7") (pin "1") (pinfunction "~{RST}_1") (pintype "input"))
    )
  )
)
